# BACKPMAN30_Charger.net
KiCad netlist of a schematic drawn in Altium Designer
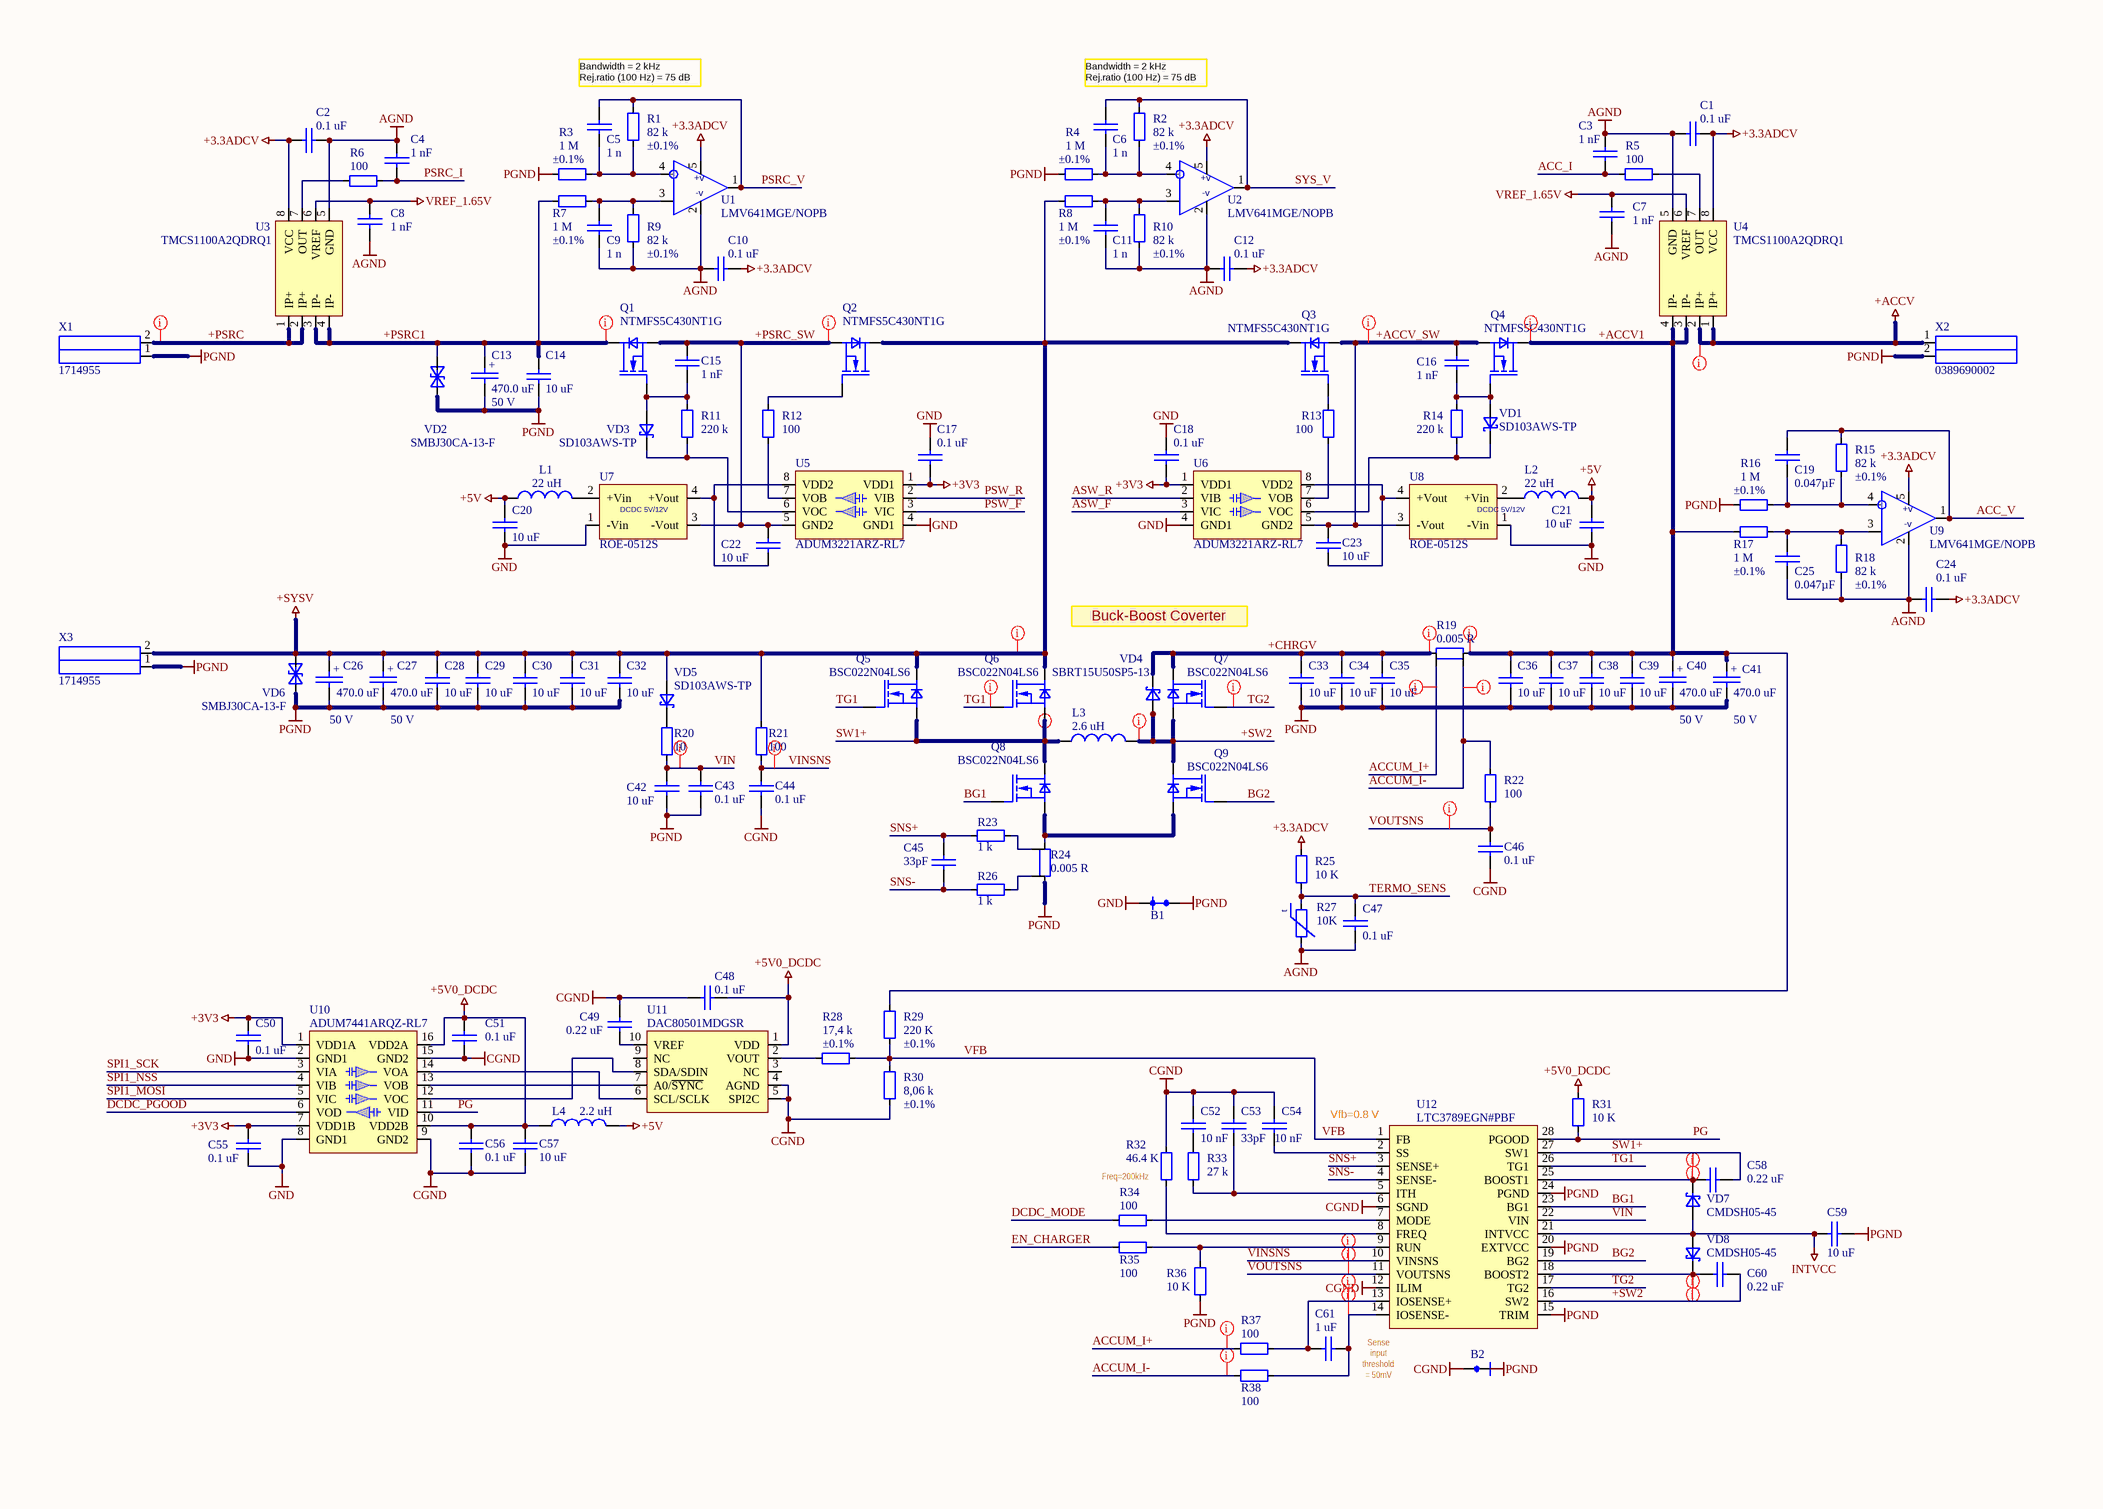
[diagram p0: BACKPMAN30_Charger.SchDoc]

(export (version "E")
  (design (tool "Eeschema 10.0.6"))
  (components
    (comp (ref "B1")
      (value "Net tie W10")
      (footprint "Net tee W 10 mm")
      (description "Net tie width 10 mm")
      (libsource (lib "ea_Mechanical") (part "Net tie W10"))
    )
    (comp (ref "B2")
      (value "Net tie 0.3mm")
      (footprint "Net tee 0.3 mm")
      (libsource (lib "ea_Mechanical") (part "Net tie 0.3mm"))
    )
    (comp (ref "C1")
      (value "0.1 uF")
      (footprint "1608[0603]")
      (description "0.1 µF ±10% 50V Ceramic Capacitor X7R 0603 (1608 Metric), -55°C ~ 125°C")
      (fields
        (field (name "MANUFACTURER") "Walsin Technology Corporation")
        (field (name "PARTNUM") "1292-1643-1-ND")
      )
      (libsource (lib "ea_Capacitors_0603") (part "0603B104K500CT"))
    )
    (comp (ref "C2")
      (value "0.1 uF")
      (footprint "1608[0603]")
      (description "0.1 µF ±10% 50V Ceramic Capacitor X7R 0603 (1608 Metric), -55°C ~ 125°C")
      (fields
        (field (name "MANUFACTURER") "Walsin Technology Corporation")
        (field (name "PARTNUM") "1292-1643-1-ND")
      )
      (libsource (lib "ea_Capacitors_0603") (part "0603B104K500CT"))
    )
    (comp (ref "C3")
      (value "1 nF")
      (footprint "0603 CAP")
      (description "1000pF, ±5%, 50V, X7R, 0603 (1608 Metric), -55°C ~ 125°C, -, General Purpose")
      (fields (field (name "PART NUMBER") "CC0603JRX7R9BB102") (field (name "MANUFACTURER") "Yageo"))
      (libsource (lib "ea_PassivComps") (part "Capacitor"))
    )
    (comp (ref "C4")
      (value "1 nF")
      (footprint "0603 CAP")
      (description "1000pF, ±5%, 50V, X7R, 0603 (1608 Metric), -55°C ~ 125°C, -, General Purpose")
      (fields (field (name "PART NUMBER") "CC0603JRX7R9BB102") (field (name "MANUFACTURER") "Yageo"))
      (libsource (lib "ea_PassivComps") (part "Capacitor"))
    )
    (comp (ref "C5")
      (value "1 n")
      (footprint "1608[0603]")
      (description "1000 pF ±1% 25V Ceramic Capacitor C0G, NP0 0603 (1608 Metric), -55°C ~ 125°C")
      (fields (field (name "MANUFACTURER") "AVX Corporation") (field (name "TOLERANCE") "±1%"))
      (libsource (lib "ea_Capacitors_0603") (part "06033A102FAT2A"))
    )
    (comp (ref "C6")
      (value "1 n")
      (footprint "1608[0603]")
      (description "1000 pF ±1% 25V Ceramic Capacitor C0G, NP0 0603 (1608 Metric), -55°C ~ 125°C")
      (fields (field (name "MANUFACTURER") "AVX Corporation") (field (name "TOLERANCE") "±1%"))
      (libsource (lib "ea_Capacitors_0603") (part "06033A102FAT2A"))
    )
    (comp (ref "C7")
      (value "1 nF")
      (footprint "0603 CAP")
      (description "1000pF, ±5%, 50V, X7R, 0603 (1608 Metric), -55°C ~ 125°C, -, General Purpose")
      (fields (field (name "PART NUMBER") "CC0603JRX7R9BB102") (field (name "MANUFACTURER") "Yageo"))
      (libsource (lib "ea_PassivComps") (part "Capacitor"))
    )
    (comp (ref "C8")
      (value "1 nF")
      (footprint "0603 CAP")
      (description "1000pF, ±5%, 50V, X7R, 0603 (1608 Metric), -55°C ~ 125°C, -, General Purpose")
      (fields (field (name "PART NUMBER") "CC0603JRX7R9BB102") (field (name "MANUFACTURER") "Yageo"))
      (libsource (lib "ea_PassivComps") (part "Capacitor"))
    )
    (comp (ref "C9")
      (value "1 n")
      (footprint "1608[0603]")
      (description "1000 pF ±1% 25V Ceramic Capacitor C0G, NP0 0603 (1608 Metric), -55°C ~ 125°C")
      (fields (field (name "MANUFACTURER") "AVX Corporation") (field (name "TOLERANCE") "±1%"))
      (libsource (lib "ea_Capacitors_0603") (part "06033A102FAT2A"))
    )
    (comp (ref "C10")
      (value "0.1 uF")
      (footprint "1608[0603]")
      (description "0.1 µF ±10% 50V Ceramic Capacitor X7R 0603 (1608 Metric), -55°C ~ 125°C")
      (fields
        (field (name "MANUFACTURER") "Walsin Technology Corporation")
        (field (name "PARTNUM") "1292-1643-1-ND")
      )
      (libsource (lib "ea_Capacitors_0603") (part "0603B104K500CT"))
    )
    (comp (ref "C11")
      (value "1 n")
      (footprint "1608[0603]")
      (description "1000 pF ±1% 25V Ceramic Capacitor C0G, NP0 0603 (1608 Metric), -55°C ~ 125°C")
      (fields (field (name "MANUFACTURER") "AVX Corporation") (field (name "TOLERANCE") "±1%"))
      (libsource (lib "ea_Capacitors_0603") (part "06033A102FAT2A"))
    )
    (comp (ref "C12")
      (value "0.1 uF")
      (footprint "1608[0603]")
      (description "0.1 µF ±10% 50V Ceramic Capacitor X7R 0603 (1608 Metric), -55°C ~ 125°C")
      (fields
        (field (name "MANUFACTURER") "Walsin Technology Corporation")
        (field (name "PARTNUM") "1292-1643-1-ND")
      )
      (libsource (lib "ea_Capacitors_0603") (part "0603B104K500CT"))
    )
    (comp (ref "C13")
      (value "470.0 uF")
      (footprint "Through Hole 12.5/20/5")
      (fields
        (field (name "MANUFACTURER") "Panasonic Electronic Components")
        (field (name "TOLERANCE") "+-20%")
        (field (name "PARTNUM") "P12400-ND")
        (field (name "VOLTAGE") "50 V")
      )
      (libsource (lib "ea_Capacitors_ThroughHole") (part "EEU-FM1H471"))
    )
    (comp (ref "C14")
      (value "10 uF")
      (footprint "3225[1210]")
      (description "10 µF ±10%, 50V, Ceramic Capacitor X7R, 1210 (3225 Metric), -55°C ~ 125°C")
      (fields
        (field (name "MANUFACTURER") "CAL-CHIP ELECTRONICS, INC.")
        (field (name "PARTNUM") "2571-GMC32X7R106K50NTTR-ND")
      )
      (libsource (lib "ea_Capacitors_1210") (part "GMC32X7R106K50NT"))
    )
    (comp (ref "C15")
      (value "1 nF")
      (footprint "0603 CAP")
      (description "1000pF, ±5%, 50V, X7R, 0603 (1608 Metric), -55°C ~ 125°C, -, General Purpose")
      (fields (field (name "PART NUMBER") "CC0603JRX7R9BB102") (field (name "MANUFACTURER") "Yageo"))
      (libsource (lib "ea_PassivComps") (part "Capacitor"))
    )
    (comp (ref "C16")
      (value "1 nF")
      (footprint "0603 CAP")
      (description "1000pF, ±5%, 50V, X7R, 0603 (1608 Metric), -55°C ~ 125°C, -, General Purpose")
      (fields (field (name "PART NUMBER") "CC0603JRX7R9BB102") (field (name "MANUFACTURER") "Yageo"))
      (libsource (lib "ea_PassivComps") (part "Capacitor"))
    )
    (comp (ref "C17")
      (value "0.1 uF")
      (footprint "1608[0603]")
      (description "0.1 µF ±10% 50V Ceramic Capacitor X7R 0603 (1608 Metric), -55°C ~ 125°C")
      (fields
        (field (name "TOLERANCE") "+-10%")
        (field (name "MANUFACTURER") "Walsin Technology Corporation")
      )
      (libsource (lib "ea_Capacitors_0603") (part "0603B104K500CT"))
    )
    (comp (ref "C18")
      (value "0.1 uF")
      (footprint "1608[0603]")
      (description "0.1 µF ±10% 50V Ceramic Capacitor X7R 0603 (1608 Metric), -55°C ~ 125°C")
      (fields
        (field (name "TOLERANCE") "+-10%")
        (field (name "MANUFACTURER") "Walsin Technology Corporation")
      )
      (libsource (lib "ea_Capacitors_0603") (part "0603B104K500CT"))
    )
    (comp (ref "C19")
      (value "0.047µF")
      (footprint "0603 CAP")
      (description "0.047µF, ±5%, 50V, X7R, 0603 (1608 Metric), -55°C ~ 125°C, -, General Purpose")
      (fields (field (name "PART NUMBER") "CC0603JRX7R9BB473") (field (name "MANUFACTURER") "Yageo"))
      (libsource (lib "ea_PassivComps") (part "Capacitor"))
    )
    (comp (ref "C20")
      (value "10 uF")
      (footprint "3225[1210]")
      (description "10 µF ±10%, 50V, Ceramic Capacitor X7R, 1210 (3225 Metric), -55°C ~ 125°C")
      (fields
        (field (name "MANUFACTURER") "CAL-CHIP ELECTRONICS, INC.")
        (field (name "PARTNUM") "2571-GMC32X7R106K50NTTR-ND")
      )
      (libsource (lib "ea_Capacitors_1210") (part "GMC32X7R106K50NT"))
    )
    (comp (ref "C21")
      (value "10 uF")
      (footprint "3225[1210]")
      (description "10 µF ±10%, 50V, Ceramic Capacitor X7R, 1210 (3225 Metric), -55°C ~ 125°C")
      (fields
        (field (name "MANUFACTURER") "CAL-CHIP ELECTRONICS, INC.")
        (field (name "PARTNUM") "2571-GMC32X7R106K50NTTR-ND")
      )
      (libsource (lib "ea_Capacitors_1210") (part "GMC32X7R106K50NT"))
    )
    (comp (ref "C22")
      (value "10 uF")
      (footprint "3225[1210]")
      (description "10 µF ±10%, 50V, Ceramic Capacitor X7R, 1210 (3225 Metric), -55°C ~ 125°C")
      (fields
        (field (name "MANUFACTURER") "CAL-CHIP ELECTRONICS, INC.")
        (field (name "PARTNUM") "2571-GMC32X7R106K50NTTR-ND")
      )
      (libsource (lib "ea_Capacitors_1210") (part "GMC32X7R106K50NT"))
    )
    (comp (ref "C23")
      (value "10 uF")
      (footprint "3225[1210]")
      (description "10 µF ±10%, 50V, Ceramic Capacitor X7R, 1210 (3225 Metric), -55°C ~ 125°C")
      (fields
        (field (name "MANUFACTURER") "CAL-CHIP ELECTRONICS, INC.")
        (field (name "PARTNUM") "2571-GMC32X7R106K50NTTR-ND")
      )
      (libsource (lib "ea_Capacitors_1210") (part "GMC32X7R106K50NT"))
    )
    (comp (ref "C24")
      (value "0.1 uF")
      (footprint "1608[0603]")
      (description "0.1 µF ±10% 50V Ceramic Capacitor X7R 0603 (1608 Metric), -55°C ~ 125°C")
      (fields
        (field (name "MANUFACTURER") "Walsin Technology Corporation")
        (field (name "PARTNUM") "1292-1643-1-ND")
      )
      (libsource (lib "ea_Capacitors_0603") (part "0603B104K500CT"))
    )
    (comp (ref "C25")
      (value "0.047µF")
      (footprint "0603 CAP")
      (description "0.047µF, ±5%, 50V, X7R, 0603 (1608 Metric), -55°C ~ 125°C, -, General Purpose")
      (fields (field (name "PART NUMBER") "CC0603JRX7R9BB473") (field (name "MANUFACTURER") "Yageo"))
      (libsource (lib "ea_PassivComps") (part "Capacitor"))
    )
    (comp (ref "C26")
      (value "470.0 uF")
      (footprint "Through Hole 12.5/20/5")
      (fields
        (field (name "MANUFACTURER") "Panasonic Electronic Components")
        (field (name "TOLERANCE") "+-20%")
        (field (name "PARTNUM") "P12400-ND")
        (field (name "VOLTAGE") "50 V")
      )
      (libsource (lib "ea_Capacitors_ThroughHole") (part "EEU-FM1H471"))
    )
    (comp (ref "C27")
      (value "470.0 uF")
      (footprint "Through Hole 12.5/20/5")
      (fields
        (field (name "MANUFACTURER") "Panasonic Electronic Components")
        (field (name "TOLERANCE") "+-20%")
        (field (name "PARTNUM") "P12400-ND")
        (field (name "VOLTAGE") "50 V")
      )
      (libsource (lib "ea_Capacitors_ThroughHole") (part "EEU-FM1H471"))
    )
    (comp (ref "C28")
      (value "10 uF")
      (footprint "3225[1210]")
      (description "10 µF ±10%, 50V, Ceramic Capacitor X7R, 1210 (3225 Metric), -55°C ~ 125°C")
      (fields
        (field (name "MANUFACTURER") "CAL-CHIP ELECTRONICS, INC.")
        (field (name "PARTNUM") "2571-GMC32X7R106K50NTTR-ND")
      )
      (libsource (lib "ea_Capacitors_1210") (part "GMC32X7R106K50NT"))
    )
    (comp (ref "C29")
      (value "10 uF")
      (footprint "3225[1210]")
      (description "10 µF ±10%, 50V, Ceramic Capacitor X7R, 1210 (3225 Metric), -55°C ~ 125°C")
      (fields
        (field (name "MANUFACTURER") "CAL-CHIP ELECTRONICS, INC.")
        (field (name "PARTNUM") "2571-GMC32X7R106K50NTTR-ND")
      )
      (libsource (lib "ea_Capacitors_1210") (part "GMC32X7R106K50NT"))
    )
    (comp (ref "C30")
      (value "10 uF")
      (footprint "3225[1210]")
      (description "10 µF ±10%, 50V, Ceramic Capacitor X7R, 1210 (3225 Metric), -55°C ~ 125°C")
      (fields
        (field (name "MANUFACTURER") "CAL-CHIP ELECTRONICS, INC.")
        (field (name "PARTNUM") "2571-GMC32X7R106K50NTTR-ND")
      )
      (libsource (lib "ea_Capacitors_1210") (part "GMC32X7R106K50NT"))
    )
    (comp (ref "C31")
      (value "10 uF")
      (footprint "3225[1210]")
      (description "10 µF ±10%, 50V, Ceramic Capacitor X7R, 1210 (3225 Metric), -55°C ~ 125°C")
      (fields
        (field (name "MANUFACTURER") "CAL-CHIP ELECTRONICS, INC.")
        (field (name "PARTNUM") "2571-GMC32X7R106K50NTTR-ND")
      )
      (libsource (lib "ea_Capacitors_1210") (part "GMC32X7R106K50NT"))
    )
    (comp (ref "C32")
      (value "10 uF")
      (footprint "3225[1210]")
      (description "10 µF ±10%, 50V, Ceramic Capacitor X7R, 1210 (3225 Metric), -55°C ~ 125°C")
      (fields
        (field (name "MANUFACTURER") "CAL-CHIP ELECTRONICS, INC.")
        (field (name "PARTNUM") "2571-GMC32X7R106K50NTTR-ND")
      )
      (libsource (lib "ea_Capacitors_1210") (part "GMC32X7R106K50NT"))
    )
    (comp (ref "C33")
      (value "10 uF")
      (footprint "3225[1210]")
      (description "10 µF ±10%, 50V, Ceramic Capacitor X7R, 1210 (3225 Metric), -55°C ~ 125°C")
      (fields
        (field (name "MANUFACTURER") "CAL-CHIP ELECTRONICS, INC.")
        (field (name "PARTNUM") "2571-GMC32X7R106K50NTTR-ND")
      )
      (libsource (lib "ea_Capacitors_1210") (part "GMC32X7R106K50NT"))
    )
    (comp (ref "C34")
      (value "10 uF")
      (footprint "3225[1210]")
      (description "10 µF ±10%, 50V, Ceramic Capacitor X7R, 1210 (3225 Metric), -55°C ~ 125°C")
      (fields
        (field (name "MANUFACTURER") "CAL-CHIP ELECTRONICS, INC.")
        (field (name "PARTNUM") "2571-GMC32X7R106K50NTTR-ND")
      )
      (libsource (lib "ea_Capacitors_1210") (part "GMC32X7R106K50NT"))
    )
    (comp (ref "C35")
      (value "10 uF")
      (footprint "3225[1210]")
      (description "10 µF ±10%, 50V, Ceramic Capacitor X7R, 1210 (3225 Metric), -55°C ~ 125°C")
      (fields
        (field (name "MANUFACTURER") "CAL-CHIP ELECTRONICS, INC.")
        (field (name "PARTNUM") "2571-GMC32X7R106K50NTTR-ND")
      )
      (libsource (lib "ea_Capacitors_1210") (part "GMC32X7R106K50NT"))
    )
    (comp (ref "C36")
      (value "10 uF")
      (footprint "3225[1210]")
      (description "10 µF ±10%, 50V, Ceramic Capacitor X7R, 1210 (3225 Metric), -55°C ~ 125°C")
      (fields
        (field (name "MANUFACTURER") "CAL-CHIP ELECTRONICS, INC.")
        (field (name "PARTNUM") "2571-GMC32X7R106K50NTTR-ND")
      )
      (libsource (lib "ea_Capacitors_1210") (part "GMC32X7R106K50NT"))
    )
    (comp (ref "C37")
      (value "10 uF")
      (footprint "3225[1210]")
      (description "10 µF ±10%, 50V, Ceramic Capacitor X7R, 1210 (3225 Metric), -55°C ~ 125°C")
      (fields
        (field (name "MANUFACTURER") "CAL-CHIP ELECTRONICS, INC.")
        (field (name "PARTNUM") "2571-GMC32X7R106K50NTTR-ND")
      )
      (libsource (lib "ea_Capacitors_1210") (part "GMC32X7R106K50NT"))
    )
    (comp (ref "C38")
      (value "10 uF")
      (footprint "3225[1210]")
      (description "10 µF ±10%, 50V, Ceramic Capacitor X7R, 1210 (3225 Metric), -55°C ~ 125°C")
      (fields
        (field (name "MANUFACTURER") "CAL-CHIP ELECTRONICS, INC.")
        (field (name "PARTNUM") "2571-GMC32X7R106K50NTTR-ND")
      )
      (libsource (lib "ea_Capacitors_1210") (part "GMC32X7R106K50NT"))
    )
    (comp (ref "C39")
      (value "10 uF")
      (footprint "3225[1210]")
      (description "10 µF ±10%, 50V, Ceramic Capacitor X7R, 1210 (3225 Metric), -55°C ~ 125°C")
      (fields
        (field (name "MANUFACTURER") "CAL-CHIP ELECTRONICS, INC.")
        (field (name "PARTNUM") "2571-GMC32X7R106K50NTTR-ND")
      )
      (libsource (lib "ea_Capacitors_1210") (part "GMC32X7R106K50NT"))
    )
    (comp (ref "C40")
      (value "470.0 uF")
      (footprint "Through Hole 12.5/20/5")
      (fields
        (field (name "MANUFACTURER") "Panasonic Electronic Components")
        (field (name "TOLERANCE") "+-20%")
        (field (name "PARTNUM") "P12400-ND")
        (field (name "VOLTAGE") "50 V")
      )
      (libsource (lib "ea_Capacitors_ThroughHole") (part "EEU-FM1H471"))
    )
    (comp (ref "C41")
      (value "470.0 uF")
      (footprint "Through Hole 12.5/20/5")
      (fields
        (field (name "MANUFACTURER") "Panasonic Electronic Components")
        (field (name "TOLERANCE") "+-20%")
        (field (name "PARTNUM") "P12400-ND")
        (field (name "VOLTAGE") "50 V")
      )
      (libsource (lib "ea_Capacitors_ThroughHole") (part "EEU-FM1H471"))
    )
    (comp (ref "C42")
      (value "10 uF")
      (footprint "3225[1210]")
      (description "10 µF ±10%, 50V, Ceramic Capacitor X7R, 1210 (3225 Metric), -55°C ~ 125°C")
      (fields
        (field (name "MANUFACTURER") "CAL-CHIP ELECTRONICS, INC.")
        (field (name "PARTNUM") "2571-GMC32X7R106K50NTTR-ND")
      )
      (libsource (lib "ea_Capacitors_1210") (part "GMC32X7R106K50NT"))
    )
    (comp (ref "C43")
      (value "0.1 uF")
      (footprint "1608[0603]")
      (description "0.1 µF ±10% 50V Ceramic Capacitor X7R 0603 (1608 Metric), -55°C ~ 125°C")
      (fields
        (field (name "MANUFACTURER") "Walsin Technology Corporation")
        (field (name "PARTNUM") "1292-1643-1-ND")
      )
      (libsource (lib "ea_Capacitors_0603") (part "0603B104K500CT"))
    )
    (comp (ref "C44")
      (value "0.1 uF")
      (footprint "1608[0603]")
      (description "0.1 µF ±10% 50V Ceramic Capacitor X7R 0603 (1608 Metric), -55°C ~ 125°C")
      (fields
        (field (name "MANUFACTURER") "Walsin Technology Corporation")
        (field (name "PARTNUM") "1292-1643-1-ND")
      )
      (libsource (lib "ea_Capacitors_0603") (part "0603B104K500CT"))
    )
    (comp (ref "C45")
      (value "33pF")
      (footprint "0603 CAP")
      (description "33pF, ±5%, 50V, C0G, NP0, 0603 (1608 Metric), -55°C ~ 125°C, -, General Purpose")
      (fields
        (field (name "PART NUMBER") "885012006054")
        (field (name "MANUFACTURER") "Wurth Electronics Inc.")
      )
      (libsource (lib "ea_PassivComps") (part "Capacitor"))
    )
    (comp (ref "C46")
      (value "0.1 uF")
      (footprint "1608[0603]")
      (description "0.1 µF ±10% 50V Ceramic Capacitor X7R 0603 (1608 Metric), -55°C ~ 125°C")
      (fields
        (field (name "MANUFACTURER") "Walsin Technology Corporation")
        (field (name "PARTNUM") "1292-1643-1-ND")
      )
      (libsource (lib "ea_Capacitors_0603") (part "0603B104K500CT"))
    )
    (comp (ref "C47")
      (value "0.1 uF")
      (footprint "1608[0603]")
      (description "0.1 µF ±10% 50V Ceramic Capacitor X7R 0603 (1608 Metric), -55°C ~ 125°C")
      (fields
        (field (name "MANUFACTURER") "Walsin Technology Corporation")
        (field (name "PARTNUM") "1292-1643-1-ND")
      )
      (libsource (lib "ea_Capacitors_0603") (part "0603B104K500CT"))
    )
    (comp (ref "C48")
      (value "0.1 uF")
      (footprint "1608[0603]")
      (description "0.1 µF ±10% 50V Ceramic Capacitor X7R 0603 (1608 Metric), -55°C ~ 125°C")
      (fields
        (field (name "MANUFACTURER") "Walsin Technology Corporation")
        (field (name "PARTNUM") "1292-1643-1-ND")
      )
      (libsource (lib "ea_Capacitors_0603") (part "0603B104K500CT"))
    )
    (comp (ref "C49")
      (value "0.22 uF")
      (footprint "1608[0603]")
      (description "0.22 uF, ±10% 50V Ceramic Capacitor X7R, Low ESL 0603 (1608 Metric), -55°C ~ 125°C")
      (fields (field (name "MANUFACTURER") "TDK Corporation") (field (name "PARTNUM") "445-7408-1-ND"))
      (libsource (lib "ea_Capacitors_0603") (part "C1608X7R1H224K080AB"))
    )
    (comp (ref "C50")
      (value "0.1 uF")
      (footprint "1608[0603]")
      (description "0.1 µF ±10% 50V Ceramic Capacitor X7R 0603 (1608 Metric), -55°C ~ 125°C")
      (fields
        (field (name "TOLERANCE") "+-10%")
        (field (name "MANUFACTURER") "Walsin Technology Corporation")
      )
      (libsource (lib "ea_Capacitors_0603") (part "0603B104K500CT"))
    )
    (comp (ref "C51")
      (value "0.1 uF")
      (footprint "1608[0603]")
      (description "0.1 µF ±10% 50V Ceramic Capacitor X7R 0603 (1608 Metric), -55°C ~ 125°C")
      (fields
        (field (name "TOLERANCE") "+-10%")
        (field (name "MANUFACTURER") "Walsin Technology Corporation")
      )
      (libsource (lib "ea_Capacitors_0603") (part "0603B104K500CT"))
    )
    (comp (ref "C52")
      (value "10 nF")
      (footprint "1608[0603]")
      (description "10 nF, ±20%, 50V,  Ceramic Capacitor X7R 0603 (1608 Metric), -55°C ~ 125°C")
      (fields
        (field (name "MANUFACTURER") "CAL-CHIP ELECTRONICS, INC.")
        (field (name "PARTNUM") "2571-GMC10X7R103M50NTTR-ND")
      )
      (libsource (lib "ea_Capacitors_0603") (part "GMC10X7R103M50NT"))
    )
    (comp (ref "C53")
      (value "33pF")
      (footprint "0603 CAP")
      (description "33pF, ±5%, 50V, C0G, NP0, 0603 (1608 Metric), -55°C ~ 125°C, -, General Purpose")
      (fields
        (field (name "PART NUMBER") "885012006054")
        (field (name "MANUFACTURER") "Wurth Electronics Inc.")
      )
      (libsource (lib "ea_PassivComps") (part "Capacitor"))
    )
    (comp (ref "C54")
      (value "10 nF")
      (footprint "1608[0603]")
      (description "10 nF, ±20%, 50V,  Ceramic Capacitor X7R 0603 (1608 Metric), -55°C ~ 125°C")
      (fields
        (field (name "MANUFACTURER") "CAL-CHIP ELECTRONICS, INC.")
        (field (name "PARTNUM") "2571-GMC10X7R103M50NTTR-ND")
      )
      (libsource (lib "ea_Capacitors_0603") (part "GMC10X7R103M50NT"))
    )
    (comp (ref "C55")
      (value "0.1 uF")
      (footprint "1608[0603]")
      (description "0.1 µF ±10% 50V Ceramic Capacitor X7R 0603 (1608 Metric), -55°C ~ 125°C")
      (fields
        (field (name "TOLERANCE") "+-10%")
        (field (name "MANUFACTURER") "Walsin Technology Corporation")
      )
      (libsource (lib "ea_Capacitors_0603") (part "0603B104K500CT"))
    )
    (comp (ref "C56")
      (value "0.1 uF")
      (footprint "1608[0603]")
      (description "0.1 µF ±10% 50V Ceramic Capacitor X7R 0603 (1608 Metric), -55°C ~ 125°C")
      (fields
        (field (name "TOLERANCE") "+-10%")
        (field (name "MANUFACTURER") "Walsin Technology Corporation")
      )
      (libsource (lib "ea_Capacitors_0603") (part "0603B104K500CT"))
    )
    (comp (ref "C57")
      (value "10 uF")
      (footprint "2012[0805]")
      (description "10 µF ±10%, 25V, Ceramic Capacitor X5R 0805 (2012 Metric),  -55°C ~ 85°C")
      (fields (field (name "MANUFACTURER") "Murata Electronics") (field (name "PARTNUM") "490-5523-1-ND"))
      (libsource (lib "ea_Capacitors_0805") (part "GRM21BR61E106KA73L"))
    )
    (comp (ref "C58")
      (value "0.22 uF")
      (footprint "1608[0603]")
      (description "0.22 uF, ±10% 50V Ceramic Capacitor X7R, Low ESL 0603 (1608 Metric), -55°C ~ 125°C")
      (fields (field (name "MANUFACTURER") "TDK Corporation") (field (name "PARTNUM") "445-7408-1-ND"))
      (libsource (lib "ea_Capacitors_0603") (part "C1608X7R1H224K080AB"))
    )
    (comp (ref "C59")
      (value "10 uF")
      (footprint "2012[0805]")
      (description "10 µF ±10%, 25V, Ceramic Capacitor X5R 0805 (2012 Metric),  -55°C ~ 85°C")
      (fields (field (name "MANUFACTURER") "Murata Electronics") (field (name "PARTNUM") "490-5523-1-ND"))
      (libsource (lib "ea_Capacitors_0805") (part "GRM21BR61E106KA73L"))
    )
    (comp (ref "C60")
      (value "0.22 uF")
      (footprint "1608[0603]")
      (description "0.22 uF, ±10% 50V Ceramic Capacitor X7R, Low ESL 0603 (1608 Metric), -55°C ~ 125°C")
      (fields (field (name "MANUFACTURER") "TDK Corporation") (field (name "PARTNUM") "445-7408-1-ND"))
      (libsource (lib "ea_Capacitors_0603") (part "C1608X7R1H224K080AB"))
    )
    (comp (ref "C61")
      (value "1 uF")
      (footprint "1608[0603]")
      (description "1 uF, ±10%, Low ESL, 50V, Ceramic Capacitor X5R 0603 (1608 Metric), -55°C ~ 85°C")
      (fields (field (name "MANUFACTURER") "Venkel") (field (name "PARTNUM") "445-7468-1-ND"))
      (libsource (lib "ea_Capacitors_0603") (part "C1608X5R1H105K080AB"))
    )
    (comp (ref "L1")
      (value "22 uH")
      (footprint "2518")
      (description "22 µH Unshielded Wirewound Inductor, 490 mA, 560mOhm, 1007 (2518 Metric)")
      (fields (field (name "MANUFACTURER") "Taiyo Yuden") (field (name "PARTNUM") "587-2439-1-ND"))
      (libsource (lib "") (part "BRC2518T220K_1"))
    )
    (comp (ref "L2")
      (value "22 uH")
      (footprint "2518")
      (description "22 µH Unshielded Wirewound Inductor, 490 mA, 560mOhm, 1007 (2518 Metric)")
      (fields (field (name "MANUFACTURER") "Taiyo Yuden") (field (name "PARTNUM") "587-2439-1-ND"))
      (libsource (lib "ea_Inductors") (part "BRC2518T220K"))
    )
    (comp (ref "L3")
      (value "2.6 uH")
      (footprint "7443556260   Wurth Elektronik")
      (description "2.6 uH, 31.5 A, ±20%, 1.58 mOhm, -40°C ~ 125°C")
      (fields (field (name "MANUFACTURER") "Würth Elektronik") (field (name "PARTNUM") "732-2170-1-ND"))
      (libsource (lib "ea_Inductors") (part "7443556260"))
    )
    (comp (ref "L4")
      (value "2.2 uH")
      (footprint "LSQPB3225")
      (description "Inductors 2.2 uH, 1.6 A, 0.078 Ohms, ±20% -40°C ~ 105°C, 1210 (3225 Metric)")
      (fields (field (name "MANUFACTURER") "Taiyo Yuden") (field (name "PARTNUM") "587-2165-1-ND"))
      (libsource (lib "ea_Inductors") (part "BRL3225T2R2M"))
    )
    (comp (ref "Q1")
      (value "NTMFS5C430NT1G")
      (footprint "SO8FL Universal Footprint")
      (description "MOSFET N-CH, 35A (Ta), 185A (Tc), 40V, Vgs=±20V, 1.7 mOhm, 47nC @ 10V, 5-DFN (5x6), -55°C ~ 175°C")
      (fields
        (field (name "MANUFACTURER") "Texas Instruments")
        (field (name "PARTNUM") "NTMFS5C430NT1GOSCT-ND")
      )
      (libsource (lib "ea_MOSFET_&_drivers") (part "NTMFS5C430NT1G"))
    )
    (comp (ref "Q2")
      (value "NTMFS5C430NT1G")
      (footprint "SO8FL Universal Footprint")
      (description "MOSFET N-CH, 35A (Ta), 185A (Tc), 40V, Vgs=±20V, 1.7 mOhm, 47nC @ 10V, 5-DFN (5x6), -55°C ~ 175°C")
      (fields
        (field (name "MANUFACTURER") "Texas Instruments")
        (field (name "PARTNUM") "NTMFS5C430NT1GOSCT-ND")
      )
      (libsource (lib "ea_MOSFET_&_drivers") (part "NTMFS5C430NT1G"))
    )
    (comp (ref "Q3")
      (value "NTMFS5C430NT1G")
      (footprint "SO8FL Universal Footprint")
      (description "MOSFET N-CH, 35A (Ta), 185A (Tc), 40V, Vgs=±20V, 1.7 mOhm, 47nC @ 10V, 5-DFN (5x6), -55°C ~ 175°C")
      (fields
        (field (name "MANUFACTURER") "Texas Instruments")
        (field (name "PARTNUM") "NTMFS5C430NT1GOSCT-ND")
      )
      (libsource (lib "ea_MOSFET_&_drivers") (part "NTMFS5C430NT1G"))
    )
    (comp (ref "Q4")
      (value "NTMFS5C430NT1G")
      (footprint "SO8FL Universal Footprint")
      (description "MOSFET N-CH, 35A (Ta), 185A (Tc), 40V, Vgs=±20V, 1.7 mOhm, 47nC @ 10V, 5-DFN (5x6), -55°C ~ 175°C")
      (fields
        (field (name "MANUFACTURER") "Texas Instruments")
        (field (name "PARTNUM") "NTMFS5C430NT1GOSCT-ND")
      )
      (libsource (lib "ea_MOSFET_&_drivers") (part "NTMFS5C430NT1G"))
    )
    (comp (ref "Q5")
      (value "BSC022N04LS6")
      (footprint "SO8FL Universal Footprint")
      (description "MOSFET N-CH, 100 A, 60V, Vgs=±20V, 1.8 mOhm, 41nC @ 10V, 5-DFN (5x6), -55°C ~ 150°C")
      (fields
        (field (name "MANUFACTURER") "Infineon Technologies")
        (field (name "PARTNUM") "BSC022N04LS6ATMA1CT-ND")
      )
      (libsource (lib "") (part "BSC022N04LS6ATMA1_1"))
    )
    (comp (ref "Q6")
      (value "BSC022N04LS6")
      (footprint "SO8FL Universal Footprint")
      (description "MOSFET N-CH, 100 A, 60V, Vgs=±20V, 1.8 mOhm, 41nC @ 10V, 5-DFN (5x6), -55°C ~ 150°C")
      (fields
        (field (name "MANUFACTURER") "Infineon Technologies")
        (field (name "PARTNUM") "BSC022N04LS6ATMA1CT-ND")
      )
      (libsource (lib "") (part "BSC022N04LS6ATMA1_1"))
    )
    (comp (ref "Q7")
      (value "BSC022N04LS6")
      (footprint "SO8FL Universal Footprint")
      (description "MOSFET N-CH, 100 A, 60V, Vgs=±20V, 1.8 mOhm, 41nC @ 10V, 5-DFN (5x6), -55°C ~ 150°C")
      (fields
        (field (name "MANUFACTURER") "Infineon Technologies")
        (field (name "PARTNUM") "BSC022N04LS6ATMA1CT-ND")
      )
      (libsource (lib "ea_MOSFET_&_drivers") (part "BSC022N04LS6ATMA1"))
    )
    (comp (ref "Q8")
      (value "BSC022N04LS6")
      (footprint "SO8FL Universal Footprint")
      (description "MOSFET N-CH, 100 A, 60V, Vgs=±20V, 1.8 mOhm, 41nC @ 10V, 5-DFN (5x6), -55°C ~ 150°C")
      (fields
        (field (name "MANUFACTURER") "Infineon Technologies")
        (field (name "PARTNUM") "BSC022N04LS6ATMA1CT-ND")
      )
      (libsource (lib "") (part "BSC022N04LS6ATMA1_1"))
    )
    (comp (ref "Q9")
      (value "BSC022N04LS6")
      (footprint "SO8FL Universal Footprint")
      (description "MOSFET N-CH, 100 A, 60V, Vgs=±20V, 1.8 mOhm, 41nC @ 10V, 5-DFN (5x6), -55°C ~ 150°C")
      (fields
        (field (name "MANUFACTURER") "Infineon Technologies")
        (field (name "PARTNUM") "BSC022N04LS6ATMA1CT-ND")
      )
      (libsource (lib "ea_MOSFET_&_drivers") (part "BSC022N04LS6ATMA1"))
    )
    (comp (ref "R1")
      (value "82 k")
      (footprint "0603")
      (fields
        (field (name "MANUFACTURER") "Panasonic Electronic Components")
        (field (name "TOLERANCE") "±0.1%")
        (field (name "VOLTAGE") "75V")
        (field (name "PARTNUM") "P82KDBCT-ND")
      )
      (libsource (lib "ea_PassivComps") (part "Resistor"))
    )
    (comp (ref "R2")
      (value "82 k")
      (footprint "0603")
      (fields
        (field (name "MANUFACTURER") "Panasonic Electronic Components")
        (field (name "TOLERANCE") "±0.1%")
        (field (name "VOLTAGE") "75V")
        (field (name "PARTNUM") "P82KDBCT-ND")
      )
      (libsource (lib "ea_PassivComps") (part "Resistor"))
    )
    (comp (ref "R3")
      (value "1 M")
      (footprint "0805")
      (description "1M, ±0.1%, ±50ppm/°C, 0.125W, 1/8W Chip Resistor 0805 (2012 Metric) - Thin Film,-55°C ~ 155°C")
      (fields
        (field (name "MANUFACTURER") "YAGEO")
        (field (name "TOLERANCE") "±0.1%")
        (field (name "PARTNUM") "YAG4967CT-ND")
      )
      (libsource (lib "ea_Resistors_0805") (part "RT0805BRE071ML"))
    )
    (comp (ref "R4")
      (value "1 M")
      (footprint "0805")
      (description "1M, ±0.1%, ±50ppm/°C, 0.125W, 1/8W Chip Resistor 0805 (2012 Metric) - Thin Film,-55°C ~ 155°C")
      (fields
        (field (name "MANUFACTURER") "YAGEO")
        (field (name "TOLERANCE") "±0.1%")
        (field (name "PARTNUM") "YAG4967CT-ND")
      )
      (libsource (lib "ea_Resistors_0805") (part "RT0805BRE071ML"))
    )
    (comp (ref "R5")
      (value "100")
      (footprint "0603")
      (fields
        (field (name "MANUFACTURER") "Stackpole Electronics Inc.")
        (field (name "TOLERANCE") "±1%")
        (field (name "VOLTAGE") "75V")
      )
      (libsource (lib "") (part "Resistor_3"))
    )
    (comp (ref "R6")
      (value "100")
      (footprint "0603")
      (fields
        (field (name "MANUFACTURER") "Stackpole Electronics Inc.")
        (field (name "TOLERANCE") "±1%")
        (field (name "VOLTAGE") "75V")
      )
      (libsource (lib "") (part "Resistor_1"))
    )
    (comp (ref "R7")
      (value "1 M")
      (footprint "0805")
      (description "1M, ±0.1%, ±50ppm/°C, 0.125W, 1/8W Chip Resistor 0805 (2012 Metric) - Thin Film,-55°C ~ 155°C")
      (fields
        (field (name "MANUFACTURER") "YAGEO")
        (field (name "TOLERANCE") "±0.1%")
        (field (name "PARTNUM") "YAG4967CT-ND")
      )
      (libsource (lib "ea_Resistors_0805") (part "RT0805BRE071ML"))
    )
    (comp (ref "R8")
      (value "1 M")
      (footprint "0805")
      (description "1M, ±0.1%, ±50ppm/°C, 0.125W, 1/8W Chip Resistor 0805 (2012 Metric) - Thin Film,-55°C ~ 155°C")
      (fields
        (field (name "MANUFACTURER") "YAGEO")
        (field (name "TOLERANCE") "±0.1%")
        (field (name "PARTNUM") "YAG4967CT-ND")
      )
      (libsource (lib "ea_Resistors_0805") (part "RT0805BRE071ML"))
    )
    (comp (ref "R9")
      (value "82 k")
      (footprint "0603")
      (fields
        (field (name "MANUFACTURER") "Panasonic Electronic Components")
        (field (name "TOLERANCE") "±0.1%")
        (field (name "VOLTAGE") "75V")
        (field (name "PARTNUM") "P82KDBCT-ND")
      )
      (libsource (lib "ea_PassivComps") (part "Resistor"))
    )
    (comp (ref "R10")
      (value "82 k")
      (footprint "0603")
      (fields
        (field (name "MANUFACTURER") "Panasonic Electronic Components")
        (field (name "TOLERANCE") "±0.1%")
        (field (name "VOLTAGE") "75V")
        (field (name "PARTNUM") "P82KDBCT-ND")
      )
      (libsource (lib "ea_PassivComps") (part "Resistor"))
    )
    (comp (ref "R11")
      (value "220 k")
      (footprint "0603")
      (fields
        (field (name "MANUFACTURER") "Stackpole Electronics Inc.")
        (field (name "TOLERANCE") "±1%")
        (field (name "VOLTAGE") "75V")
      )
      (libsource (lib "ea_PassivComps") (part "Resistor"))
    )
    (comp (ref "R12")
      (value "100")
      (footprint "0603")
      (fields
        (field (name "MANUFACTURER") "Stackpole Electronics Inc.")
        (field (name "TOLERANCE") "±1%")
        (field (name "VOLTAGE") "75V")
      )
      (libsource (lib "ea_PassivComps") (part "Resistor"))
    )
    (comp (ref "R13")
      (value "100")
      (footprint "0603")
      (fields
        (field (name "MANUFACTURER") "Stackpole Electronics Inc.")
        (field (name "TOLERANCE") "±1%")
        (field (name "VOLTAGE") "75V")
      )
      (libsource (lib "") (part "Resistor_3"))
    )
    (comp (ref "R14")
      (value "220 k")
      (footprint "0603")
      (fields
        (field (name "MANUFACTURER") "Stackpole Electronics Inc.")
        (field (name "TOLERANCE") "±1%")
        (field (name "VOLTAGE") "75V")
      )
      (libsource (lib "") (part "Resistor_3"))
    )
    (comp (ref "R15")
      (value "82 k")
      (footprint "0603")
      (fields
        (field (name "MANUFACTURER") "Panasonic Electronic Components")
        (field (name "TOLERANCE") "±0.1%")
        (field (name "VOLTAGE") "75V")
        (field (name "PARTNUM") "P82KDBCT-ND")
      )
      (libsource (lib "ea_PassivComps") (part "Resistor"))
    )
    (comp (ref "R16")
      (value "1 M")
      (footprint "0805")
      (description "1M, ±0.1%, ±50ppm/°C, 0.125W, 1/8W Chip Resistor 0805 (2012 Metric) - Thin Film,-55°C ~ 155°C")
      (fields
        (field (name "MANUFACTURER") "YAGEO")
        (field (name "TOLERANCE") "±0.1%")
        (field (name "PARTNUM") "YAG4967CT-ND")
      )
      (libsource (lib "ea_Resistors_0805") (part "RT0805BRE071ML"))
    )
    (comp (ref "R17")
      (value "1 M")
      (footprint "0805")
      (description "1M, ±0.1%, ±50ppm/°C, 0.125W, 1/8W Chip Resistor 0805 (2012 Metric) - Thin Film,-55°C ~ 155°C")
      (fields
        (field (name "MANUFACTURER") "YAGEO")
        (field (name "TOLERANCE") "±0.1%")
        (field (name "PARTNUM") "YAG4967CT-ND")
      )
      (libsource (lib "ea_Resistors_0805") (part "RT0805BRE071ML"))
    )
    (comp (ref "R18")
      (value "82 k")
      (footprint "0603")
      (fields
        (field (name "MANUFACTURER") "Panasonic Electronic Components")
        (field (name "TOLERANCE") "±0.1%")
        (field (name "VOLTAGE") "75V")
        (field (name "PARTNUM") "P82KDBCT-ND")
      )
      (libsource (lib "ea_PassivComps") (part "Resistor"))
    )
    (comp (ref "R19")
      (value "0.005 R")
      (footprint "FC4L110")
      (description "Curr.sens.res. 0.005 OHM 5W 1% , 4320 (50110 Metric)")
      (fields (field (name "MANUFACTURER") "Ohmite") (field (name "TOLERANCE") "1%"))
      (libsource (lib "") (part "FC4L110R005FER_1"))
    )
    (comp (ref "R20")
      (value "10")
      (footprint "0805")
      (fields
        (field (name "MANUFACTURER") "Stackpole Electronics Inc.")
        (field (name "TOLERANCE") "±1%")
        (field (name "VOLTAGE") "150V")
      )
      (libsource (lib "ea_PassivComps") (part "Resistor"))
    )
    (comp (ref "R21")
      (value "100")
      (footprint "0603")
      (fields
        (field (name "MANUFACTURER") "Stackpole Electronics Inc.")
        (field (name "TOLERANCE") "±1%")
        (field (name "VOLTAGE") "75V")
      )
      (libsource (lib "ea_PassivComps") (part "Resistor"))
    )
    (comp (ref "R22")
      (value "100")
      (footprint "0603")
      (fields
        (field (name "MANUFACTURER") "Stackpole Electronics Inc.")
        (field (name "TOLERANCE") "±1%")
        (field (name "VOLTAGE") "75V")
      )
      (libsource (lib "ea_PassivComps") (part "Resistor"))
    )
    (comp (ref "R23")
      (value "1 k")
      (footprint "0603")
      (fields
        (field (name "MANUFACTURER") "Stackpole Electronics Inc.")
        (field (name "TOLERANCE") "±1%")
        (field (name "VOLTAGE") "75V")
      )
      (libsource (lib "") (part "Resistor_2"))
    )
    (comp (ref "R24")
      (value "0.005 R")
      (footprint "FC4L110")
      (description "Curr.sens.res. 0.005 OHM 5W 1% , 4320 (50110 Metric)")
      (fields (field (name "MANUFACTURER") "Ohmite") (field (name "TOLERANCE") "1%"))
      (libsource (lib "ea_Resistors") (part "FC4L110R005FER"))
    )
    (comp (ref "R25")
      (value "10 K")
      (footprint "0603")
      (fields
        (field (name "MANUFACTURER") "Stackpole Electronics Inc")
        (field (name "TOLERANCE") "1%")
        (field (name "PARTNUM") "RMCF0603FT10K0CT-ND")
      )
      (libsource (lib "") (part "RMCF0603FT10K0_1"))
    )
    (comp (ref "R26")
      (value "1 k")
      (footprint "0603")
      (fields
        (field (name "MANUFACTURER") "Stackpole Electronics Inc.")
        (field (name "TOLERANCE") "±1%")
        (field (name "VOLTAGE") "75V")
      )
      (libsource (lib "") (part "Resistor_2"))
    )
    (comp (ref "R27")
      (value "10K")
      (footprint "0603")
      (description "NTC Thermistor 10k, B25/50 3380K, ±0.5%,  0603 (1608 Metric), -40°C ~ 125°C")
      (fields (field (name "MANUFACTURER") "TDK Corporation") (field (name "PARTNUM") "445-174519-1-ND"))
      (libsource (lib "ea_TermoSensors") (part "NTCG163JX103DTDS"))
    )
    (comp (ref "R28")
      (value "17,4 k")
      (footprint "0603")
      (fields
        (field (name "MANUFACTURER") "Panasonic Electronic Components")
        (field (name "TOLERANCE") "±0.1%")
        (field (name "VOLTAGE") "75V")
        (field (name "PARTNUM") "P17.4KDBCT-ND")
      )
      (libsource (lib "") (part "Resistor_3"))
    )
    (comp (ref "R29")
      (value "220 K")
      (footprint "0603")
      (description "220 kOhms ±0.1% 0.125W, 1/8W Chip Resistor 0603 (1608 Metric), Thin Film")
      (fields
        (field (name "MANUFACTURER") "Vishay Dale")
        (field (name "TOLERANCE") "±0.1%")
        (field (name "PARTNUM") "541-3175-1-ND")
      )
      (libsource (lib "ea_Resistors_0603") (part "TNPW0603220KBEEA"))
    )
    (comp (ref "R30")
      (value "8,06 k")
      (footprint "0603")
      (fields
        (field (name "MANUFACTURER") "Panasonic Electronic Components")
        (field (name "TOLERANCE") "±0.1%")
        (field (name "VOLTAGE") "75V")
        (field (name "PARTNUM") "P8.06KDBCT-ND")
      )
      (libsource (lib "ea_PassivComps") (part "Resistor"))
    )
    (comp (ref "R31")
      (value "10 K")
      (footprint "0603")
      (fields
        (field (name "MANUFACTURER") "Stackpole Electronics Inc")
        (field (name "TOLERANCE") "1%")
        (field (name "PARTNUM") "RMCF0603FT10K0CT-ND")
      )
      (libsource (lib "ea_Resistors_0603") (part "RMCF0603FT10K0"))
    )
    (comp (ref "R32")
      (value "46.4 K")
      (footprint "0603")
      (description "46.4 kOhms ±1% 0.1W, 1/10W Chip Resistor 0603 (1608 Metric) Moisture Resistant Thick Film")
      (fields (field (name "MANUFACTURER") "YAGEO") (field (name "TOLERANCE") "1%"))
      (libsource (lib "ea_Resistors_0603") (part "RC0603FR-0746K4L"))
    )
    (comp (ref "R33")
      (value "27 k")
      (footprint "0603")
      (fields
        (field (name "MANUFACTURER") "Stackpole Electronics Inc.")
        (field (name "TOLERANCE") "±1%")
        (field (name "VOLTAGE") "75V")
      )
      (libsource (lib "ea_PassivComps") (part "Resistor"))
    )
    (comp (ref "R34")
      (value "100")
      (footprint "0603")
      (fields
        (field (name "MANUFACTURER") "Stackpole Electronics Inc.")
        (field (name "TOLERANCE") "±1%")
        (field (name "VOLTAGE") "75V")
      )
      (libsource (lib "") (part "Resistor_1"))
    )
    (comp (ref "R35")
      (value "100")
      (footprint "0603")
      (fields
        (field (name "MANUFACTURER") "Stackpole Electronics Inc.")
        (field (name "TOLERANCE") "±1%")
        (field (name "VOLTAGE") "75V")
      )
      (libsource (lib "") (part "Resistor_1"))
    )
    (comp (ref "R36")
      (value "10 K")
      (footprint "0603")
      (fields
        (field (name "MANUFACTURER") "Stackpole Electronics Inc")
        (field (name "TOLERANCE") "1%")
        (field (name "PARTNUM") "RMCF0603FT10K0CT-ND")
      )
      (libsource (lib "") (part "RMCF0603FT10K0_1"))
    )
    (comp (ref "R37")
      (value "100")
      (footprint "0603")
      (fields
        (field (name "MANUFACTURER") "Stackpole Electronics Inc.")
        (field (name "TOLERANCE") "±1%")
        (field (name "VOLTAGE") "75V")
      )
      (libsource (lib "") (part "Resistor_1"))
    )
    (comp (ref "R38")
      (value "100")
      (footprint "0603")
      (fields
        (field (name "MANUFACTURER") "Stackpole Electronics Inc.")
        (field (name "TOLERANCE") "±1%")
        (field (name "VOLTAGE") "75V")
      )
      (libsource (lib "") (part "Resistor_1"))
    )
    (comp (ref "U1")
      (value "LMV641MGE/NOPB")
      (footprint "SOT-353 ON Semi")
      (description "OpAmp,  Rail-to-Rail,  10MHz, VSS 2.7V ~ 12V, Vofs 30µV,  SC-70-5, -40°C ~ 125°C")
      (fields
        (field (name "MANUFACTURER") "Texas Instruments")
        (field (name "PARTNUM") "LMV641MGE/NOPBCT-ND")
      )
      (libsource (lib "ea_IC_OPAmps_AnComparators") (part "LMV641MGE/NOPB"))
    )
    (comp (ref "U2")
      (value "LMV641MGE/NOPB")
      (footprint "SOT-353 ON Semi")
      (description "OpAmp,  Rail-to-Rail,  10MHz, VSS 2.7V ~ 12V, Vofs 30µV,  SC-70-5, -40°C ~ 125°C")
      (fields
        (field (name "MANUFACTURER") "Texas Instruments")
        (field (name "PARTNUM") "LMV641MGE/NOPBCT-ND")
      )
      (libsource (lib "ea_IC_OPAmps_AnComparators") (part "LMV641MGE/NOPB"))
    )
    (comp (ref "U3")
      (value "TMCS1100A2QDRQ1")
      (footprint "8-SOIC Linear")
      (fields
        (field (name "MANUFACTURER") "Texas Instruments")
        (field (name "PARTNUM") "595-TMCS1100A2QDRQ1")
      )
      (libsource (lib "ea_IC_sensors") (part "TMCS1100A2QDRQ1"))
    )
    (comp (ref "U4")
      (value "TMCS1100A2QDRQ1")
      (footprint "8-SOIC Linear")
      (fields
        (field (name "MANUFACTURER") "Texas Instruments")
        (field (name "PARTNUM") "595-TMCS1100A2QDRQ1")
      )
      (libsource (lib "") (part "TMCS1100A2QDRQ1_1"))
    )
    (comp (ref "U5")
      (value "ADUM3221ARZ-RL7")
      (footprint "8-SOIC Linear")
      (description "4A Gate Driver Magnetic Coupling 2500Vrms 2 Channel 8-SOIC, -40°C ~ 125°C")
      (fields
        (field (name "MANUFACTURER") "Analog Devices Inc.")
        (field (name "PARTNUM") "ADUM3221ARZ-RL7CT-ND")
      )
      (libsource (lib "") (part "ADUM3221ARZ-RL7_1"))
    )
    (comp (ref "U6")
      (value "ADUM3221ARZ-RL7")
      (footprint "8-SOIC Linear")
      (description "4A Gate Driver Magnetic Coupling 2500Vrms 2 Channel 8-SOIC, -40°C ~ 125°C")
      (fields
        (field (name "MANUFACTURER") "Analog Devices Inc.")
        (field (name "PARTNUM") "ADUM3221ARZ-RL7CT-ND")
      )
      (libsource (lib "ea_IC_Isolated_Interfaces") (part "ADUM3221ARZ-RL7"))
    )
    (comp (ref "U7")
      (value "ROE-0512S")
      (footprint "Recom 4-SIP module")
      (description "Isolated Module DC DC Converter 1 Output 12V - - 84mA 4.5V - 5.5V Input")
      (fields (field (name "MANUFACTURER") "Recom Power") (field (name "PARTNUM") "ROE-0512S-ND"))
      (libsource (lib "") (part "ROE-0512S_1"))
    )
    (comp (ref "U8")
      (value "ROE-0512S")
      (footprint "Recom 4-SIP module")
      (description "Isolated Module DC DC Converter 1 Output 12V - - 84mA 4.5V - 5.5V Input")
      (fields (field (name "MANUFACTURER") "Recom Power") (field (name "PARTNUM") "ROE-0512S-ND"))
      (libsource (lib "ea_PowerSources") (part "ROE-0512S"))
    )
    (comp (ref "U9")
      (value "LMV641MGE/NOPB")
      (footprint "SOT-353 ON Semi")
      (description "OpAmp,  Rail-to-Rail,  10MHz, VSS 2.7V ~ 12V, Vofs 30µV,  SC-70-5, -40°C ~ 125°C")
      (fields
        (field (name "MANUFACTURER") "Texas Instruments")
        (field (name "PARTNUM") "LMV641MGE/NOPBCT-ND")
      )
      (libsource (lib "ea_IC_OPAmps_AnComparators") (part "LMV641MGE/NOPB"))
    )
    (comp (ref "U10")
      (value "ADUM7441ARQZ-RL7")
      (footprint "QSOP-16 AD")
      (fields
        (field (name "MANUFACTURER") "Analog Devices Inc.")
        (field (name "PARTNUM") "ADUM7441ARQZ-RL7CT-ND")
      )
      (libsource (lib "ea_IC_Isolated_Interfaces") (part "ADUM7441ARQZ-RL7"))
    )
    (comp (ref "U11")
      (value "DAC80501MDGSR")
      (footprint "10-Lead Plastic MSOP Linear")
      (description "16 Bit Digital to Analog Converter, I²C, SPI, 10-VSSOP,  -40°C ~ 125°C")
      (fields
        (field (name "MANUFACTURER") "Texas Instruments")
        (field (name "PARTNUM") "296-DAC80501MDGSRCT-ND")
      )
      (libsource (lib "ea_IC_DAC") (part "DAC80501MDGSR"))
    )
    (comp (ref "U12")
      (value "LTC3789EGN#PBF")
      (footprint "28-Lead Plastic SSOP Linear")
      (fields
        (field (name "MANUFACTURER") "Linear Technology/Analog Devices")
        (field (name "PARTNUM") "LTC3789EGN#PBF-ND")
      )
      (libsource (lib "ea_IC_Power_Reg_Ref_Sw") (part "LTC3789EGN#PBF"))
    )
    (comp (ref "VD1")
      (value "SD103AWS-TP")
      (footprint "SOD323")
      (description "Diode Schottky 40 V 350mA Surface Mount SOD-323, -65°C ~ 125°C")
      (fields
        (field (name "PARTNAME") "SD103AWS-TP")
        (field (name "MANUFACTURER") "Micro Commercial Co")
        (field (name "PARTNUM") "SD103AWSTPMSCT-ND")
      )
      (libsource (lib "ea_Diodes") (part "SD103AWS-TP"))
    )
    (comp (ref "VD2")
      (value "SMBJ30CA-13-F")
      (footprint "DO-214AA_SMBJ BI")
      (description "TVS 600W, Vbr=33.3V, Vcl=48.4V,  Bidirectional, SMB, -55°C ~ 150°C")
      (fields
        (field (name "MANUFACTURER") "Diodes Incorporated")
        (field (name "PARTNUM") "SMBJ30CA-FDICT-ND")
      )
      (libsource (lib "ea_TVS_protection") (part "SMBJ30CA-13-F"))
    )
    (comp (ref "VD3")
      (value "SD103AWS-TP")
      (footprint "SOD323")
      (description "Diode Schottky 40 V 350mA Surface Mount SOD-323, -65°C ~ 125°C")
      (fields
        (field (name "PARTNAME") "SD103AWS-TP")
        (field (name "MANUFACTURER") "Micro Commercial Co")
        (field (name "PARTNUM") "SD103AWSTPMSCT-ND")
      )
      (libsource (lib "ea_Diodes") (part "SD103AWS-TP"))
    )
    (comp (ref "VD4")
      (value "SBRT15U50SP5-13")
      (footprint "PowerDI 5")
      (description "Schottky Power Rectifier 15A, 50V, 470mV @ 15A, SMA, -65°C ~ 150°C")
      (fields
        (field (name "MANUFACTURER") "Diodes Incorporated")
        (field (name "PARTNUM") "SBRT15U50SP5-13DICT-ND")
      )
      (libsource (lib "ea_Diodes") (part "SBRT15U50SP5-13"))
    )
    (comp (ref "VD5")
      (value "SD103AWS-TP")
      (footprint "SOD323")
      (description "Diode Schottky 40 V 350mA Surface Mount SOD-323, -65°C ~ 125°C")
      (fields
        (field (name "PARTNAME") "SD103AWS-TP")
        (field (name "MANUFACTURER") "Micro Commercial Co")
        (field (name "PARTNUM") "SD103AWSTPMSCT-ND")
      )
      (libsource (lib "ea_Diodes") (part "SD103AWS-TP"))
    )
    (comp (ref "VD6")
      (value "SMBJ30CA-13-F")
      (footprint "DO-214AA_SMBJ BI")
      (description "TVS 600W, Vbr=33.3V, Vcl=48.4V,  Bidirectional, SMB, -55°C ~ 150°C")
      (fields
        (field (name "MANUFACTURER") "Diodes Incorporated")
        (field (name "PARTNUM") "SMBJ30CA-FDICT-ND")
      )
      (libsource (lib "ea_TVS_protection") (part "SMBJ30CA-13-F"))
    )
    (comp (ref "VD7")
      (value "CMDSH05-45 TR PBFREE")
      (footprint "SOD323")
      (description "Diode Schottky 45 V 500mA Surface Mount SOD-323, -65°C ~ 125°C")
      (fields
        (field (name "PARTNAME") "CMDSH05-45")
        (field (name "MANUFACTURER") "Central Semiconductor Corp")
        (field (name "PARTNUM") "1514-CMDSH05-45TRPBFREECT-ND")
      )
      (libsource (lib "ea_Diodes") (part "CMDSH05-45 TR PBFREE"))
    )
    (comp (ref "VD8")
      (value "CMDSH05-45 TR PBFREE")
      (footprint "SOD323")
      (description "Diode Schottky 45 V 500mA Surface Mount SOD-323, -65°C ~ 125°C")
      (fields
        (field (name "PARTNAME") "CMDSH05-45")
        (field (name "MANUFACTURER") "Central Semiconductor Corp")
        (field (name "PARTNUM") "1514-CMDSH05-45TRPBFREECT-ND")
      )
      (libsource (lib "ea_Diodes") (part "CMDSH05-45 TR PBFREE"))
    )
    (comp (ref "X1")
      (value "1714955")
      (footprint "MKDS5/2-6.35")
      (description "TERMINAL BLOCK, 2WAY, 6.35 mm, 32A, 500V")
      (fields (field (name "MANUFACTURER") "Phoenix Contact") (field (name "PARTNUM") "277-1269-ND"))
      (libsource (lib "ea_PhoenixContacts") (part "1714955"))
    )
    (comp (ref "X2")
      (value "0389690002")
      (footprint "Molex 389690002")
      (description "2 Circuit 0.500\" (12.70mm) Barrier Block Connector Screws with Captive Plate, 50A, 600V, 8-20AWG")
      (fields (field (name "MANUFACTURER") "Molex") (field (name "PARTNUM") "WM7469-ND"))
      (libsource (lib "ea_Connectors_Power") (part "0389690002"))
    )
    (comp (ref "X3")
      (value "1714955")
      (footprint "MKDS5/2-6.35")
      (description "TERMINAL BLOCK, 2WAY, 6.35 mm, 32A, 500V")
      (fields (field (name "MANUFACTURER") "Phoenix Contact") (field (name "PARTNUM") "277-1269-ND"))
      (libsource (lib "ea_PhoenixContacts") (part "1714955"))
    )
  )
  (nets
    (net (code "1") (name "+3.3ADCV") (class "Default")
      (node (ref "C1") (pin "2") (pinfunction "2_2") (pintype "passive"))
      (node (ref "C10") (pin "1") (pinfunction "1_1") (pintype "passive"))
      (node (ref "C12") (pin "1") (pinfunction "1_1") (pintype "passive"))
      (node (ref "C2") (pin "2") (pinfunction "2_2") (pintype "passive"))
      (node (ref "C24") (pin "1") (pinfunction "1_1") (pintype "passive"))
      (node (ref "R25") (pin "2") (pinfunction "2_2") (pintype "passive"))
      (node (ref "U1") (pin "5") (pinfunction "V+_5") (pintype "power_in"))
      (node (ref "U2") (pin "5") (pinfunction "V+_5") (pintype "power_in"))
      (node (ref "U3") (pin "8") (pinfunction "VCC_8") (pintype "passive"))
      (node (ref "U4") (pin "8") (pinfunction "VCC_8") (pintype "passive"))
      (node (ref "U9") (pin "5") (pinfunction "V+_5") (pintype "power_in"))
    )
    (net (code "2") (name "+3V3") (class "Default")
      (node (ref "C17") (pin "1") (pinfunction "1_1") (pintype "passive"))
      (node (ref "C18") (pin "1") (pinfunction "1_1") (pintype "passive"))
      (node (ref "C50") (pin "2") (pinfunction "2_2") (pintype "passive"))
      (node (ref "C55") (pin "2") (pinfunction "2_2") (pintype "passive"))
      (node (ref "U10") (pin "1") (pinfunction "VDD1A_1") (pintype "passive"))
      (node (ref "U10") (pin "7") (pinfunction "VDD1B_7") (pintype "passive"))
      (node (ref "U5") (pin "1") (pinfunction "VDD1_1") (pintype "passive"))
      (node (ref "U6") (pin "1") (pinfunction "VDD1_1") (pintype "passive"))
    )
    (net (code "3") (name "+5V") (class "Default")
      (node (ref "C20") (pin "1") (pinfunction "1_1") (pintype "passive"))
      (node (ref "C21") (pin "1") (pinfunction "1_1") (pintype "passive"))
      (node (ref "L1") (pin "1") (pinfunction "1_1") (pintype "passive"))
      (node (ref "L2") (pin "1") (pinfunction "1_1") (pintype "passive"))
      (node (ref "L4") (pin "2") (pinfunction "2_2") (pintype "passive"))
    )
    (net (code "4") (name "+5V0_DCDC") (class "Default")
      (node (ref "C48") (pin "1") (pinfunction "1_1") (pintype "passive"))
      (node (ref "C51") (pin "2") (pinfunction "2_2") (pintype "passive"))
      (node (ref "C56") (pin "2") (pinfunction "2_2") (pintype "passive"))
      (node (ref "C57") (pin "2") (pinfunction "2_2") (pintype "passive"))
      (node (ref "L4") (pin "1") (pinfunction "1_1") (pintype "passive"))
      (node (ref "R31") (pin "1") (pinfunction "1_1") (pintype "passive"))
      (node (ref "U10") (pin "10") (pinfunction "VDD2B_10") (pintype "passive"))
      (node (ref "U10") (pin "16") (pinfunction "VDD2A_16") (pintype "passive"))
      (node (ref "U11") (pin "1") (pinfunction "VDD_1") (pintype "passive"))
    )
    (net (code "5") (name "+ACCV") (class "Default")
      (node (ref "U4") (pin "1") (pinfunction "IP+_1") (pintype "passive"))
      (node (ref "U4") (pin "2") (pinfunction "IP+_2") (pintype "passive"))
      (node (ref "X2") (pin "1") (pinfunction "1_1") (pintype "passive"))
    )
    (net (code "6") (name "+SYSV") (class "Default")
      (node (ref "C26") (pin "1") (pinfunction "1_1") (pintype "passive"))
      (node (ref "C27") (pin "1") (pinfunction "1_1") (pintype "passive"))
      (node (ref "C28") (pin "1") (pinfunction "1_1") (pintype "passive"))
      (node (ref "C29") (pin "1") (pinfunction "1_1") (pintype "passive"))
      (node (ref "C30") (pin "1") (pinfunction "1_1") (pintype "passive"))
      (node (ref "C31") (pin "1") (pinfunction "1_1") (pintype "passive"))
      (node (ref "C32") (pin "1") (pinfunction "1_1") (pintype "passive"))
      (node (ref "Q2") (pin "3") (pinfunction "D_3") (pintype "passive"))
      (node (ref "Q3") (pin "3") (pinfunction "D_3") (pintype "passive"))
      (node (ref "Q5") (pin "3") (pinfunction "D_3") (pintype "passive"))
      (node (ref "Q6") (pin "3") (pinfunction "D_3") (pintype "passive"))
      (node (ref "R21") (pin "2") (pinfunction "2_2") (pintype "passive"))
      (node (ref "R8") (pin "1") (pinfunction "1_1") (pintype "passive"))
      (node (ref "VD5") (pin "1") (pinfunction "A_1") (pintype "passive"))
      (node (ref "VD6") (pin "2") (pinfunction "A_2") (pintype "passive"))
      (node (ref "X3") (pin "2") (pinfunction "2_2") (pintype "passive"))
    )
    (net (code "7") (name "/+ACCV1") (class "Default")
      (node (ref "C36") (pin "1") (pinfunction "1_1") (pintype "passive"))
      (node (ref "C37") (pin "1") (pinfunction "1_1") (pintype "passive"))
      (node (ref "C38") (pin "1") (pinfunction "1_1") (pintype "passive"))
      (node (ref "C39") (pin "1") (pinfunction "1_1") (pintype "passive"))
      (node (ref "C40") (pin "1") (pinfunction "1_1") (pintype "passive"))
      (node (ref "C41") (pin "1") (pinfunction "1_1") (pintype "passive"))
      (node (ref "Q4") (pin "3") (pinfunction "D_3") (pintype "passive"))
      (node (ref "R17") (pin "1") (pinfunction "1_1") (pintype "passive"))
      (node (ref "R19") (pin "2") (pinfunction "2_2") (pintype "passive"))
      (node (ref "R29") (pin "2") (pinfunction "2_2") (pintype "passive"))
      (node (ref "U4") (pin "3") (pinfunction "IP-_3") (pintype "passive"))
      (node (ref "U4") (pin "4") (pinfunction "IP-_4") (pintype "passive"))
    )
    (net (code "8") (name "/+ACCV_SW") (class "Default")
      (node (ref "C16") (pin "2") (pinfunction "2_2") (pintype "passive"))
      (node (ref "C23") (pin "1") (pinfunction "1_1") (pintype "passive"))
      (node (ref "Q3") (pin "2") (pinfunction "S_2") (pintype "passive"))
      (node (ref "Q4") (pin "2") (pinfunction "S_2") (pintype "passive"))
      (node (ref "U6") (pin "5") (pinfunction "GND2_5") (pintype "passive"))
      (node (ref "U8") (pin "3") (pinfunction "-Vout_3") (pintype "passive"))
    )
    (net (code "9") (name "/+CHRGV") (class "Default")
      (node (ref "C33") (pin "1") (pinfunction "1_1") (pintype "passive"))
      (node (ref "C34") (pin "1") (pinfunction "1_1") (pintype "passive"))
      (node (ref "C35") (pin "1") (pinfunction "1_1") (pintype "passive"))
      (node (ref "Q7") (pin "3") (pinfunction "D_3") (pintype "passive"))
      (node (ref "R19") (pin "1") (pinfunction "1_1") (pintype "passive"))
      (node (ref "VD4") (pin "3") (pinfunction "3_3") (pintype "passive"))
    )
    (net (code "10") (name "/+PSRC") (class "Default")
      (node (ref "U3") (pin "1") (pinfunction "IP+_1") (pintype "passive"))
      (node (ref "U3") (pin "2") (pinfunction "IP+_2") (pintype "passive"))
      (node (ref "X1") (pin "2") (pinfunction "2_2") (pintype "passive"))
    )
    (net (code "11") (name "/+PSRC1") (class "Default")
      (node (ref "C13") (pin "1") (pinfunction "1_1") (pintype "passive"))
      (node (ref "C14") (pin "1") (pinfunction "1_1") (pintype "passive"))
      (node (ref "Q1") (pin "3") (pinfunction "D_3") (pintype "passive"))
      (node (ref "R7") (pin "1") (pinfunction "1_1") (pintype "passive"))
      (node (ref "U3") (pin "3") (pinfunction "IP-_3") (pintype "passive"))
      (node (ref "U3") (pin "4") (pinfunction "IP-_4") (pintype "passive"))
      (node (ref "VD2") (pin "2") (pinfunction "A_2") (pintype "passive"))
    )
    (net (code "12") (name "/+PSRC_SW") (class "Default")
      (node (ref "C15") (pin "2") (pinfunction "2_2") (pintype "passive"))
      (node (ref "C22") (pin "1") (pinfunction "1_1") (pintype "passive"))
      (node (ref "Q1") (pin "2") (pinfunction "S_2") (pintype "passive"))
      (node (ref "Q2") (pin "2") (pinfunction "S_2") (pintype "passive"))
      (node (ref "U5") (pin "5") (pinfunction "GND2_5") (pintype "passive"))
      (node (ref "U7") (pin "3") (pinfunction "-Vout_3") (pintype "passive"))
    )
    (net (code "13") (name "/+SW2") (class "Default")
      (node (ref "C60") (pin "2") (pinfunction "2_2") (pintype "passive"))
      (node (ref "L3") (pin "2") (pinfunction "2_2") (pintype "passive"))
      (node (ref "Q7") (pin "2") (pinfunction "S_2") (pintype "passive"))
      (node (ref "Q9") (pin "3") (pinfunction "D_3") (pintype "passive"))
      (node (ref "U12") (pin "16") (pinfunction "SW2_16") (pintype "passive"))
      (node (ref "VD4") (pin "1") (pinfunction "1_1") (pintype "passive"))
      (node (ref "VD4") (pin "2") (pinfunction "2_2") (pintype "passive"))
    )
    (net (code "14") (name "/ACCUM_I+") (class "Default")
      (node (ref "R19") (pin "3") (pinfunction "1_3") (pintype "passive"))
      (node (ref "R37") (pin "2") (pinfunction "2_2") (pintype "passive"))
    )
    (net (code "15") (name "/ACCUM_I-") (class "Default")
      (node (ref "R19") (pin "4") (pinfunction "1_4") (pintype "passive"))
      (node (ref "R22") (pin "2") (pinfunction "2_2") (pintype "passive"))
      (node (ref "R38") (pin "2") (pinfunction "2_2") (pintype "passive"))
    )
    (net (code "16") (name "/ACC_I") (class "Default")
      (node (ref "C3") (pin "1") (pinfunction "1_1") (pintype "passive"))
      (node (ref "R5") (pin "1") (pinfunction "1_1") (pintype "passive"))
    )
    (net (code "17") (name "/ACC_V") (class "Default")
      (node (ref "C19") (pin "1") (pinfunction "1_1") (pintype "passive"))
      (node (ref "R15") (pin "2") (pinfunction "2_2") (pintype "passive"))
      (node (ref "U9") (pin "1") (pinfunction "OUT_1") (pintype "passive"))
    )
    (net (code "18") (name "/ASW_F") (class "Default")
      (node (ref "U6") (pin "3") (pinfunction "VIC_3") (pintype "passive"))
    )
    (net (code "19") (name "/ASW_R") (class "Default")
      (node (ref "U6") (pin "2") (pinfunction "VIB_2") (pintype "passive"))
    )
    (net (code "20") (name "/BG1") (class "Default")
      (node (ref "Q8") (pin "1") (pinfunction "G_1") (pintype "passive"))
      (node (ref "U12") (pin "23") (pinfunction "BG1_23") (pintype "passive"))
    )
    (net (code "21") (name "/BG2") (class "Default")
      (node (ref "Q9") (pin "1") (pinfunction "G_1") (pintype "passive"))
      (node (ref "U12") (pin "19") (pinfunction "BG2_19") (pintype "passive"))
    )
    (net (code "22") (name "/DCDC_MODE") (class "Default")
      (node (ref "R34") (pin "2") (pinfunction "2_2") (pintype "passive"))
    )
    (net (code "23") (name "/DCDC_PGOOD") (class "Default")
      (node (ref "U10") (pin "6") (pinfunction "VOD_6") (pintype "passive"))
    )
    (net (code "24") (name "/EN_CHARGER") (class "Default")
      (node (ref "R35") (pin "2") (pinfunction "2_2") (pintype "passive"))
    )
    (net (code "25") (name "/PG") (class "Default")
      (node (ref "R31") (pin "2") (pinfunction "2_2") (pintype "passive"))
      (node (ref "U10") (pin "11") (pinfunction "VID_11") (pintype "passive"))
      (node (ref "U12") (pin "28") (pinfunction "PGOOD_28") (pintype "passive"))
    )
    (net (code "26") (name "/PSRC_I") (class "Default")
      (node (ref "C4") (pin "1") (pinfunction "1_1") (pintype "passive"))
      (node (ref "R6") (pin "1") (pinfunction "1_1") (pintype "passive"))
    )
    (net (code "27") (name "/PSRC_V") (class "Default")
      (node (ref "C5") (pin "1") (pinfunction "1_1") (pintype "passive"))
      (node (ref "R1") (pin "2") (pinfunction "2_2") (pintype "passive"))
      (node (ref "U1") (pin "1") (pinfunction "OUT_1") (pintype "passive"))
    )
    (net (code "28") (name "/PSW_F") (class "Default")
      (node (ref "U5") (pin "3") (pinfunction "VIC_3") (pintype "passive"))
    )
    (net (code "29") (name "/PSW_R") (class "Default")
      (node (ref "U5") (pin "2") (pinfunction "VIB_2") (pintype "passive"))
    )
    (net (code "30") (name "/SNS+") (class "Default")
      (node (ref "C45") (pin "1") (pinfunction "1_1") (pintype "passive"))
      (node (ref "R23") (pin "2") (pinfunction "2_2") (pintype "passive"))
      (node (ref "U12") (pin "3") (pinfunction "SENSE+_3") (pintype "passive"))
    )
    (net (code "31") (name "/SNS-") (class "Default")
      (node (ref "C45") (pin "2") (pinfunction "2_2") (pintype "passive"))
      (node (ref "R26") (pin "2") (pinfunction "2_2") (pintype "passive"))
      (node (ref "U12") (pin "4") (pinfunction "SENSE-_4") (pintype "passive"))
    )
    (net (code "32") (name "/SPI1_MOSI") (class "Default")
      (node (ref "U10") (pin "5") (pinfunction "VIC_5") (pintype "passive"))
    )
    (net (code "33") (name "/SPI1_NSS") (class "Default")
      (node (ref "U10") (pin "4") (pinfunction "VIB_4") (pintype "passive"))
    )
    (net (code "34") (name "/SPI1_SCK") (class "Default")
      (node (ref "U10") (pin "3") (pinfunction "VIA_3") (pintype "passive"))
    )
    (net (code "35") (name "/SW1+") (class "Default")
      (node (ref "C58") (pin "2") (pinfunction "2_2") (pintype "passive"))
      (node (ref "L3") (pin "1") (pinfunction "1_1") (pintype "passive"))
      (node (ref "Q5") (pin "2") (pinfunction "S_2") (pintype "passive"))
      (node (ref "Q6") (pin "2") (pinfunction "S_2") (pintype "passive"))
      (node (ref "Q8") (pin "3") (pinfunction "D_3") (pintype "passive"))
      (node (ref "U12") (pin "27") (pinfunction "SW1_27") (pintype "passive"))
    )
    (net (code "36") (name "/SYS_V") (class "Default")
      (node (ref "C6") (pin "1") (pinfunction "1_1") (pintype "passive"))
      (node (ref "R2") (pin "2") (pinfunction "2_2") (pintype "passive"))
      (node (ref "U2") (pin "1") (pinfunction "OUT_1") (pintype "passive"))
    )
    (net (code "37") (name "/TERMO_SENS") (class "Default")
      (node (ref "C47") (pin "1") (pinfunction "1_1") (pintype "passive"))
      (node (ref "R25") (pin "1") (pinfunction "1_1") (pintype "passive"))
      (node (ref "R27") (pin "2") (pinfunction "2_2") (pintype "passive"))
    )
    (net (code "38") (name "/TG1") (class "Default")
      (node (ref "Q5") (pin "1") (pinfunction "G_1") (pintype "passive"))
      (node (ref "Q6") (pin "1") (pinfunction "G_1") (pintype "passive"))
      (node (ref "U12") (pin "26") (pinfunction "TG1_26") (pintype "passive"))
    )
    (net (code "39") (name "/TG2") (class "Default")
      (node (ref "Q7") (pin "1") (pinfunction "G_1") (pintype "passive"))
      (node (ref "U12") (pin "17") (pinfunction "TG2_17") (pintype "passive"))
    )
    (net (code "40") (name "/VFB") (class "Default")
      (node (ref "R28") (pin "2") (pinfunction "2_2") (pintype "passive"))
      (node (ref "R29") (pin "1") (pinfunction "1_1") (pintype "passive"))
      (node (ref "R30") (pin "2") (pinfunction "2_2") (pintype "passive"))
      (node (ref "U12") (pin "1") (pinfunction "FB_1") (pintype "passive"))
    )
    (net (code "41") (name "/VIN") (class "Default")
      (node (ref "C42") (pin "1") (pinfunction "1_1") (pintype "passive"))
      (node (ref "C43") (pin "1") (pinfunction "1_1") (pintype "passive"))
      (node (ref "R20") (pin "1") (pinfunction "1_1") (pintype "passive"))
      (node (ref "U12") (pin "22") (pinfunction "VIN_22") (pintype "passive"))
    )
    (net (code "42") (name "/VINSNS") (class "Default")
      (node (ref "C44") (pin "1") (pinfunction "1_1") (pintype "passive"))
      (node (ref "R21") (pin "1") (pinfunction "1_1") (pintype "passive"))
      (node (ref "U12") (pin "10") (pinfunction "VINSNS_10") (pintype "passive"))
    )
    (net (code "43") (name "/VOUTSNS") (class "Default")
      (node (ref "C46") (pin "1") (pinfunction "1_1") (pintype "passive"))
      (node (ref "R22") (pin "1") (pinfunction "1_1") (pintype "passive"))
      (node (ref "U12") (pin "11") (pinfunction "VOUTSNS_11") (pintype "passive"))
    )
    (net (code "44") (name "AGND") (class "Default")
      (node (ref "C1") (pin "1") (pinfunction "1_1") (pintype "passive"))
      (node (ref "C10") (pin "2") (pinfunction "2_2") (pintype "passive"))
      (node (ref "C11") (pin "2") (pinfunction "2_2") (pintype "passive"))
      (node (ref "C12") (pin "2") (pinfunction "2_2") (pintype "passive"))
      (node (ref "C2") (pin "1") (pinfunction "1_1") (pintype "passive"))
      (node (ref "C24") (pin "2") (pinfunction "2_2") (pintype "passive"))
      (node (ref "C25") (pin "2") (pinfunction "2_2") (pintype "passive"))
      (node (ref "C3") (pin "2") (pinfunction "2_2") (pintype "passive"))
      (node (ref "C4") (pin "2") (pinfunction "2_2") (pintype "passive"))
      (node (ref "C47") (pin "2") (pinfunction "2_2") (pintype "passive"))
      (node (ref "C7") (pin "1") (pinfunction "1_1") (pintype "passive"))
      (node (ref "C8") (pin "1") (pinfunction "1_1") (pintype "passive"))
      (node (ref "C9") (pin "2") (pinfunction "2_2") (pintype "passive"))
      (node (ref "R10") (pin "1") (pinfunction "1_1") (pintype "passive"))
      (node (ref "R18") (pin "1") (pinfunction "1_1") (pintype "passive"))
      (node (ref "R27") (pin "1") (pinfunction "1_1") (pintype "passive"))
      (node (ref "R9") (pin "1") (pinfunction "1_1") (pintype "passive"))
      (node (ref "U1") (pin "2") (pinfunction "GND_2") (pintype "power_in"))
      (node (ref "U2") (pin "2") (pinfunction "GND_2") (pintype "power_in"))
      (node (ref "U3") (pin "5") (pinfunction "GND_5") (pintype "passive"))
      (node (ref "U4") (pin "5") (pinfunction "GND_5") (pintype "passive"))
      (node (ref "U9") (pin "2") (pinfunction "GND_2") (pintype "power_in"))
    )
    (net (code "45") (name "CGND") (class "Default")
      (node (ref "B2") (pin "2") (pinfunction "2_2") (pintype "passive"))
      (node (ref "C44") (pin "2") (pinfunction "2_2") (pintype "passive"))
      (node (ref "C46") (pin "2") (pinfunction "2_2") (pintype "passive"))
      (node (ref "C48") (pin "2") (pinfunction "2_2") (pintype "passive"))
      (node (ref "C49") (pin "1") (pinfunction "1_1") (pintype "passive"))
      (node (ref "C51") (pin "1") (pinfunction "1_1") (pintype "passive"))
      (node (ref "C52") (pin "1") (pinfunction "1_1") (pintype "passive"))
      (node (ref "C53") (pin "1") (pinfunction "1_1") (pintype "passive"))
      (node (ref "C54") (pin "1") (pinfunction "1_1") (pintype "passive"))
      (node (ref "C56") (pin "1") (pinfunction "1_1") (pintype "passive"))
      (node (ref "C57") (pin "1") (pinfunction "1_1") (pintype "passive"))
      (node (ref "R30") (pin "1") (pinfunction "1_1") (pintype "passive"))
      (node (ref "R32") (pin "1") (pinfunction "1_1") (pintype "passive"))
      (node (ref "U10") (pin "15") (pinfunction "GND2_15") (pintype "passive"))
      (node (ref "U10") (pin "9") (pinfunction "GND2_9") (pintype "passive"))
      (node (ref "U11") (pin "4") (pinfunction "AGND_4") (pintype "passive"))
      (node (ref "U11") (pin "5") (pinfunction "SPI2C_5") (pintype "passive"))
      (node (ref "U12") (pin "12") (pinfunction "ILIM_12") (pintype "passive"))
      (node (ref "U12") (pin "6") (pinfunction "SGND_6") (pintype "passive"))
    )
    (net (code "46") (name "GND") (class "Default")
      (node (ref "B1") (pin "1") (pinfunction "1_1") (pintype "passive"))
      (node (ref "C17") (pin "2") (pinfunction "2_2") (pintype "passive"))
      (node (ref "C18") (pin "2") (pinfunction "2_2") (pintype "passive"))
      (node (ref "C20") (pin "2") (pinfunction "2_2") (pintype "passive"))
      (node (ref "C21") (pin "2") (pinfunction "2_2") (pintype "passive"))
      (node (ref "C50") (pin "1") (pinfunction "1_1") (pintype "passive"))
      (node (ref "C55") (pin "1") (pinfunction "1_1") (pintype "passive"))
      (node (ref "U10") (pin "2") (pinfunction "GND1_2") (pintype "passive"))
      (node (ref "U10") (pin "8") (pinfunction "GND1_8") (pintype "passive"))
      (node (ref "U5") (pin "4") (pinfunction "GND1_4") (pintype "passive"))
      (node (ref "U6") (pin "4") (pinfunction "GND1_4") (pintype "passive"))
      (node (ref "U7") (pin "1") (pinfunction "-Vin_1") (pintype "passive"))
      (node (ref "U8") (pin "1") (pinfunction "-Vin_1") (pintype "passive"))
    )
    (net (code "47") (name "INTVCC") (class "Default")
      (node (ref "C59") (pin "1") (pinfunction "1_1") (pintype "passive"))
      (node (ref "U12") (pin "21") (pinfunction "INTVCC_21") (pintype "passive"))
      (node (ref "VD7") (pin "1") (pinfunction "A_1") (pintype "passive"))
      (node (ref "VD8") (pin "1") (pinfunction "A_1") (pintype "passive"))
    )
    (net (code "48") (name "Net-(C52-Pad2)") (class "Default")
      (node (ref "C52") (pin "2") (pinfunction "2_2") (pintype "passive"))
      (node (ref "R33") (pin "2") (pinfunction "2_2") (pintype "passive"))
    )
    (net (code "49") (name "Net-(Q1-G)") (class "Default")
      (node (ref "C15") (pin "1") (pinfunction "1_1") (pintype "passive"))
      (node (ref "Q1") (pin "1") (pinfunction "G_1") (pintype "passive"))
      (node (ref "R11") (pin "2") (pinfunction "2_2") (pintype "passive"))
      (node (ref "VD3") (pin "1") (pinfunction "A_1") (pintype "passive"))
    )
    (net (code "50") (name "Net-(Q2-G)") (class "Default")
      (node (ref "Q2") (pin "1") (pinfunction "G_1") (pintype "passive"))
      (node (ref "R12") (pin "2") (pinfunction "2_2") (pintype "passive"))
    )
    (net (code "51") (name "Net-(Q3-G)") (class "Default")
      (node (ref "Q3") (pin "1") (pinfunction "G_1") (pintype "passive"))
      (node (ref "R13") (pin "2") (pinfunction "2_2") (pintype "passive"))
    )
    (net (code "52") (name "Net-(Q4-G)") (class "Default")
      (node (ref "C16") (pin "1") (pinfunction "1_1") (pintype "passive"))
      (node (ref "Q4") (pin "1") (pinfunction "G_1") (pintype "passive"))
      (node (ref "R14") (pin "2") (pinfunction "2_2") (pintype "passive"))
      (node (ref "VD1") (pin "1") (pinfunction "A_1") (pintype "passive"))
    )
    (net (code "53") (name "Net-(Q8-S)") (class "Default")
      (node (ref "Q8") (pin "2") (pinfunction "S_2") (pintype "passive"))
      (node (ref "Q9") (pin "2") (pinfunction "S_2") (pintype "passive"))
      (node (ref "R24") (pin "1") (pinfunction "1_1") (pintype "passive"))
    )
    (net (code "54") (name "Net-(R23-Pad1)") (class "Default")
      (node (ref "R23") (pin "1") (pinfunction "1_1") (pintype "passive"))
      (node (ref "R24") (pin "3") (pinfunction "1_3") (pintype "passive"))
    )
    (net (code "55") (name "Net-(R24-1-Pad4)") (class "Default")
      (node (ref "R24") (pin "4") (pinfunction "1_4") (pintype "passive"))
      (node (ref "R26") (pin "1") (pinfunction "1_1") (pintype "passive"))
    )
    (net (code "56") (name "Net-(U1-IN+)") (class "Default")
      (node (ref "C9") (pin "1") (pinfunction "1_1") (pintype "passive"))
      (node (ref "R7") (pin "2") (pinfunction "2_2") (pintype "passive"))
      (node (ref "R9") (pin "2") (pinfunction "2_2") (pintype "passive"))
      (node (ref "U1") (pin "3") (pinfunction "IN+_3") (pintype "passive"))
    )
    (net (code "57") (name "Net-(U1-IN-)") (class "Default")
      (node (ref "C5") (pin "2") (pinfunction "2_2") (pintype "passive"))
      (node (ref "R1") (pin "1") (pinfunction "1_1") (pintype "passive"))
      (node (ref "R3") (pin "2") (pinfunction "2_2") (pintype "passive"))
      (node (ref "U1") (pin "4") (pinfunction "IN-_4") (pintype "passive"))
    )
    (net (code "58") (name "Net-(U2-IN+)") (class "Default")
      (node (ref "C11") (pin "1") (pinfunction "1_1") (pintype "passive"))
      (node (ref "R10") (pin "2") (pinfunction "2_2") (pintype "passive"))
      (node (ref "R8") (pin "2") (pinfunction "2_2") (pintype "passive"))
      (node (ref "U2") (pin "3") (pinfunction "IN+_3") (pintype "passive"))
    )
    (net (code "59") (name "Net-(U2-IN-)") (class "Default")
      (node (ref "C6") (pin "2") (pinfunction "2_2") (pintype "passive"))
      (node (ref "R2") (pin "1") (pinfunction "1_1") (pintype "passive"))
      (node (ref "R4") (pin "2") (pinfunction "2_2") (pintype "passive"))
      (node (ref "U2") (pin "4") (pinfunction "IN-_4") (pintype "passive"))
    )
    (net (code "60") (name "Net-(U3-OUT)") (class "Default")
      (node (ref "R6") (pin "2") (pinfunction "2_2") (pintype "passive"))
      (node (ref "U3") (pin "7") (pinfunction "OUT_7") (pintype "passive"))
    )
    (net (code "61") (name "Net-(U4-OUT)") (class "Default")
      (node (ref "R5") (pin "2") (pinfunction "2_2") (pintype "passive"))
      (node (ref "U4") (pin "7") (pinfunction "OUT_7") (pintype "passive"))
    )
    (net (code "62") (name "Net-(U5-VDD2)") (class "Default")
      (node (ref "C22") (pin "2") (pinfunction "2_2") (pintype "passive"))
      (node (ref "U5") (pin "8") (pinfunction "VDD2_8") (pintype "passive"))
      (node (ref "U7") (pin "4") (pinfunction "+Vout_4") (pintype "passive"))
    )
    (net (code "63") (name "Net-(U5-VOB)") (class "Default")
      (node (ref "R12") (pin "1") (pinfunction "1_1") (pintype "passive"))
      (node (ref "U5") (pin "7") (pinfunction "VOB_7") (pintype "passive"))
    )
    (net (code "64") (name "Net-(U5-VOC)") (class "Default")
      (node (ref "R11") (pin "1") (pinfunction "1_1") (pintype "passive"))
      (node (ref "U5") (pin "6") (pinfunction "VOC_6") (pintype "passive"))
      (node (ref "VD3") (pin "2") (pinfunction "C_2") (pintype "passive"))
    )
    (net (code "65") (name "Net-(U6-VDD2)") (class "Default")
      (node (ref "C23") (pin "2") (pinfunction "2_2") (pintype "passive"))
      (node (ref "U6") (pin "8") (pinfunction "VDD2_8") (pintype "passive"))
      (node (ref "U8") (pin "4") (pinfunction "+Vout_4") (pintype "passive"))
    )
    (net (code "66") (name "Net-(U6-VOB)") (class "Default")
      (node (ref "R13") (pin "1") (pinfunction "1_1") (pintype "passive"))
      (node (ref "U6") (pin "7") (pinfunction "VOB_7") (pintype "passive"))
    )
    (net (code "67") (name "Net-(U6-VOC)") (class "Default")
      (node (ref "R14") (pin "1") (pinfunction "1_1") (pintype "passive"))
      (node (ref "U6") (pin "6") (pinfunction "VOC_6") (pintype "passive"))
      (node (ref "VD1") (pin "2") (pinfunction "C_2") (pintype "passive"))
    )
    (net (code "68") (name "Net-(U7-+Vin)") (class "Default")
      (node (ref "L1") (pin "2") (pinfunction "2_2") (pintype "passive"))
      (node (ref "U7") (pin "2") (pinfunction "+Vin_2") (pintype "passive"))
    )
    (net (code "69") (name "Net-(U8-+Vin)") (class "Default")
      (node (ref "L2") (pin "2") (pinfunction "2_2") (pintype "passive"))
      (node (ref "U8") (pin "2") (pinfunction "+Vin_2") (pintype "passive"))
    )
    (net (code "70") (name "Net-(U9-IN+)") (class "Default")
      (node (ref "C25") (pin "1") (pinfunction "1_1") (pintype "passive"))
      (node (ref "R17") (pin "2") (pinfunction "2_2") (pintype "passive"))
      (node (ref "R18") (pin "2") (pinfunction "2_2") (pintype "passive"))
      (node (ref "U9") (pin "3") (pinfunction "IN+_3") (pintype "passive"))
    )
    (net (code "71") (name "Net-(U9-IN-)") (class "Default")
      (node (ref "C19") (pin "2") (pinfunction "2_2") (pintype "passive"))
      (node (ref "R15") (pin "1") (pinfunction "1_1") (pintype "passive"))
      (node (ref "R16") (pin "2") (pinfunction "2_2") (pintype "passive"))
      (node (ref "U9") (pin "4") (pinfunction "IN-_4") (pintype "passive"))
    )
    (net (code "72") (name "Net-(U10-VOA)") (class "Default")
      (node (ref "U10") (pin "14") (pinfunction "VOA_14") (pintype "passive"))
      (node (ref "U11") (pin "6") (pinfunction "SCL/SCLK_6") (pintype "passive"))
    )
    (net (code "73") (name "Net-(U10-VOB)") (class "Default")
      (node (ref "U10") (pin "13") (pinfunction "VOB_13") (pintype "passive"))
      (node (ref "U11") (pin "7") (pinfunction "A0/~{SYNC}_7") (pintype "passive"))
    )
    (net (code "74") (name "Net-(U10-VOC)") (class "Default")
      (node (ref "U10") (pin "12") (pinfunction "VOC_12") (pintype "passive"))
      (node (ref "U11") (pin "8") (pinfunction "SDA/SDIN_8") (pintype "passive"))
    )
    (net (code "75") (name "Net-(U11-VOUT)") (class "Default")
      (node (ref "R28") (pin "1") (pinfunction "1_1") (pintype "passive"))
      (node (ref "U11") (pin "2") (pinfunction "VOUT_2") (pintype "passive"))
    )
    (net (code "76") (name "Net-(U11-VREF)") (class "Default")
      (node (ref "C49") (pin "2") (pinfunction "2_2") (pintype "passive"))
      (node (ref "U11") (pin "10") (pinfunction "VREF_10") (pintype "passive"))
    )
    (net (code "77") (name "Net-(U12-BOOST1)") (class "Default")
      (node (ref "C58") (pin "1") (pinfunction "1_1") (pintype "passive"))
      (node (ref "U12") (pin "25") (pinfunction "BOOST1_25") (pintype "passive"))
      (node (ref "VD7") (pin "2") (pinfunction "C_2") (pintype "passive"))
    )
    (net (code "78") (name "Net-(U12-BOOST2)") (class "Default")
      (node (ref "C60") (pin "1") (pinfunction "1_1") (pintype "passive"))
      (node (ref "U12") (pin "18") (pinfunction "BOOST2_18") (pintype "passive"))
      (node (ref "VD8") (pin "2") (pinfunction "C_2") (pintype "passive"))
    )
    (net (code "79") (name "Net-(U12-FREQ)") (class "Default")
      (node (ref "R32") (pin "2") (pinfunction "2_2") (pintype "passive"))
      (node (ref "U12") (pin "8") (pinfunction "FREQ_8") (pintype "passive"))
    )
    (net (code "80") (name "Net-(U12-IOSENSE+)") (class "Default")
      (node (ref "C61") (pin "2") (pinfunction "2_2") (pintype "passive"))
      (node (ref "R37") (pin "1") (pinfunction "1_1") (pintype "passive"))
      (node (ref "U12") (pin "13") (pinfunction "IOSENSE+_13") (pintype "passive"))
    )
    (net (code "81") (name "Net-(U12-IOSENSE-)") (class "Default")
      (node (ref "C61") (pin "1") (pinfunction "1_1") (pintype "passive"))
      (node (ref "R38") (pin "1") (pinfunction "1_1") (pintype "passive"))
      (node (ref "U12") (pin "14") (pinfunction "IOSENSE-_14") (pintype "passive"))
    )
    (net (code "82") (name "Net-(U12-ITH)") (class "Default")
      (node (ref "C53") (pin "2") (pinfunction "2_2") (pintype "passive"))
      (node (ref "R33") (pin "1") (pinfunction "1_1") (pintype "passive"))
      (node (ref "U12") (pin "5") (pinfunction "ITH_5") (pintype "passive"))
    )
    (net (code "83") (name "Net-(U12-MODE)") (class "Default")
      (node (ref "R34") (pin "1") (pinfunction "1_1") (pintype "passive"))
      (node (ref "U12") (pin "7") (pinfunction "MODE_7") (pintype "passive"))
    )
    (net (code "84") (name "Net-(U12-RUN)") (class "Default")
      (node (ref "R35") (pin "1") (pinfunction "1_1") (pintype "passive"))
      (node (ref "R36") (pin "2") (pinfunction "2_2") (pintype "passive"))
      (node (ref "U12") (pin "9") (pinfunction "RUN_9") (pintype "passive"))
    )
    (net (code "85") (name "Net-(U12-SS)") (class "Default")
      (node (ref "C54") (pin "2") (pinfunction "2_2") (pintype "passive"))
      (node (ref "U12") (pin "2") (pinfunction "SS_2") (pintype "passive"))
    )
    (net (code "86") (name "Net-(VD5-C)") (class "Default")
      (node (ref "R20") (pin "2") (pinfunction "2_2") (pintype "passive"))
      (node (ref "VD5") (pin "2") (pinfunction "C_2") (pintype "passive"))
    )
    (net (code "87") (name "PGND") (class "Default")
      (node (ref "B1") (pin "2") (pinfunction "2_2") (pintype "passive"))
      (node (ref "B2") (pin "1") (pinfunction "1_1") (pintype "passive"))
      (node (ref "C13") (pin "2") (pinfunction "2_2") (pintype "passive"))
      (node (ref "C14") (pin "2") (pinfunction "2_2") (pintype "passive"))
      (node (ref "C26") (pin "2") (pinfunction "2_2") (pintype "passive"))
      (node (ref "C27") (pin "2") (pinfunction "2_2") (pintype "passive"))
      (node (ref "C28") (pin "2") (pinfunction "2_2") (pintype "passive"))
      (node (ref "C29") (pin "2") (pinfunction "2_2") (pintype "passive"))
      (node (ref "C30") (pin "2") (pinfunction "2_2") (pintype "passive"))
      (node (ref "C31") (pin "2") (pinfunction "2_2") (pintype "passive"))
      (node (ref "C32") (pin "2") (pinfunction "2_2") (pintype "passive"))
      (node (ref "C33") (pin "2") (pinfunction "2_2") (pintype "passive"))
      (node (ref "C34") (pin "2") (pinfunction "2_2") (pintype "passive"))
      (node (ref "C35") (pin "2") (pinfunction "2_2") (pintype "passive"))
      (node (ref "C36") (pin "2") (pinfunction "2_2") (pintype "passive"))
      (node (ref "C37") (pin "2") (pinfunction "2_2") (pintype "passive"))
      (node (ref "C38") (pin "2") (pinfunction "2_2") (pintype "passive"))
      (node (ref "C39") (pin "2") (pinfunction "2_2") (pintype "passive"))
      (node (ref "C40") (pin "2") (pinfunction "2_2") (pintype "passive"))
      (node (ref "C41") (pin "2") (pinfunction "2_2") (pintype "passive"))
      (node (ref "C42") (pin "2") (pinfunction "2_2") (pintype "passive"))
      (node (ref "C43") (pin "2") (pinfunction "2_2") (pintype "passive"))
      (node (ref "C59") (pin "2") (pinfunction "2_2") (pintype "passive"))
      (node (ref "R16") (pin "1") (pinfunction "1_1") (pintype "passive"))
      (node (ref "R24") (pin "2") (pinfunction "2_2") (pintype "passive"))
      (node (ref "R3") (pin "1") (pinfunction "1_1") (pintype "passive"))
      (node (ref "R36") (pin "1") (pinfunction "1_1") (pintype "passive"))
      (node (ref "R4") (pin "1") (pinfunction "1_1") (pintype "passive"))
      (node (ref "U12") (pin "15") (pinfunction "TRIM_15") (pintype "passive"))
      (node (ref "U12") (pin "20") (pinfunction "EXTVCC_20") (pintype "passive"))
      (node (ref "U12") (pin "24") (pinfunction "PGND_24") (pintype "passive"))
      (node (ref "VD2") (pin "1") (pinfunction "C_1") (pintype "passive"))
      (node (ref "VD6") (pin "1") (pinfunction "C_1") (pintype "passive"))
      (node (ref "X1") (pin "1") (pinfunction "1_1") (pintype "passive"))
      (node (ref "X2") (pin "2") (pinfunction "2_2") (pintype "passive"))
      (node (ref "X3") (pin "1") (pinfunction "1_1") (pintype "passive"))
    )
    (net (code "88") (name "VREF_1.65V") (class "Default")
      (node (ref "C7") (pin "2") (pinfunction "2_2") (pintype "passive"))
      (node (ref "C8") (pin "2") (pinfunction "2_2") (pintype "passive"))
      (node (ref "U3") (pin "6") (pinfunction "VREF_6") (pintype "passive"))
      (node (ref "U4") (pin "6") (pinfunction "VREF_6") (pintype "passive"))
    )
    (net (code "89") (name "unconnected-(U11-NC-Pad3)") (class "Default")
      (node (ref "U11") (pin "3") (pinfunction "NC_3") (pintype "passive"))
    )
    (net (code "90") (name "unconnected-(U11-NC-Pad9)") (class "Default")
      (node (ref "U11") (pin "9") (pinfunction "NC_9") (pintype "passive"))
    )
  )
)
